# dw08a2s.net
KiCad netlist of a schematic drawn in EAGLE
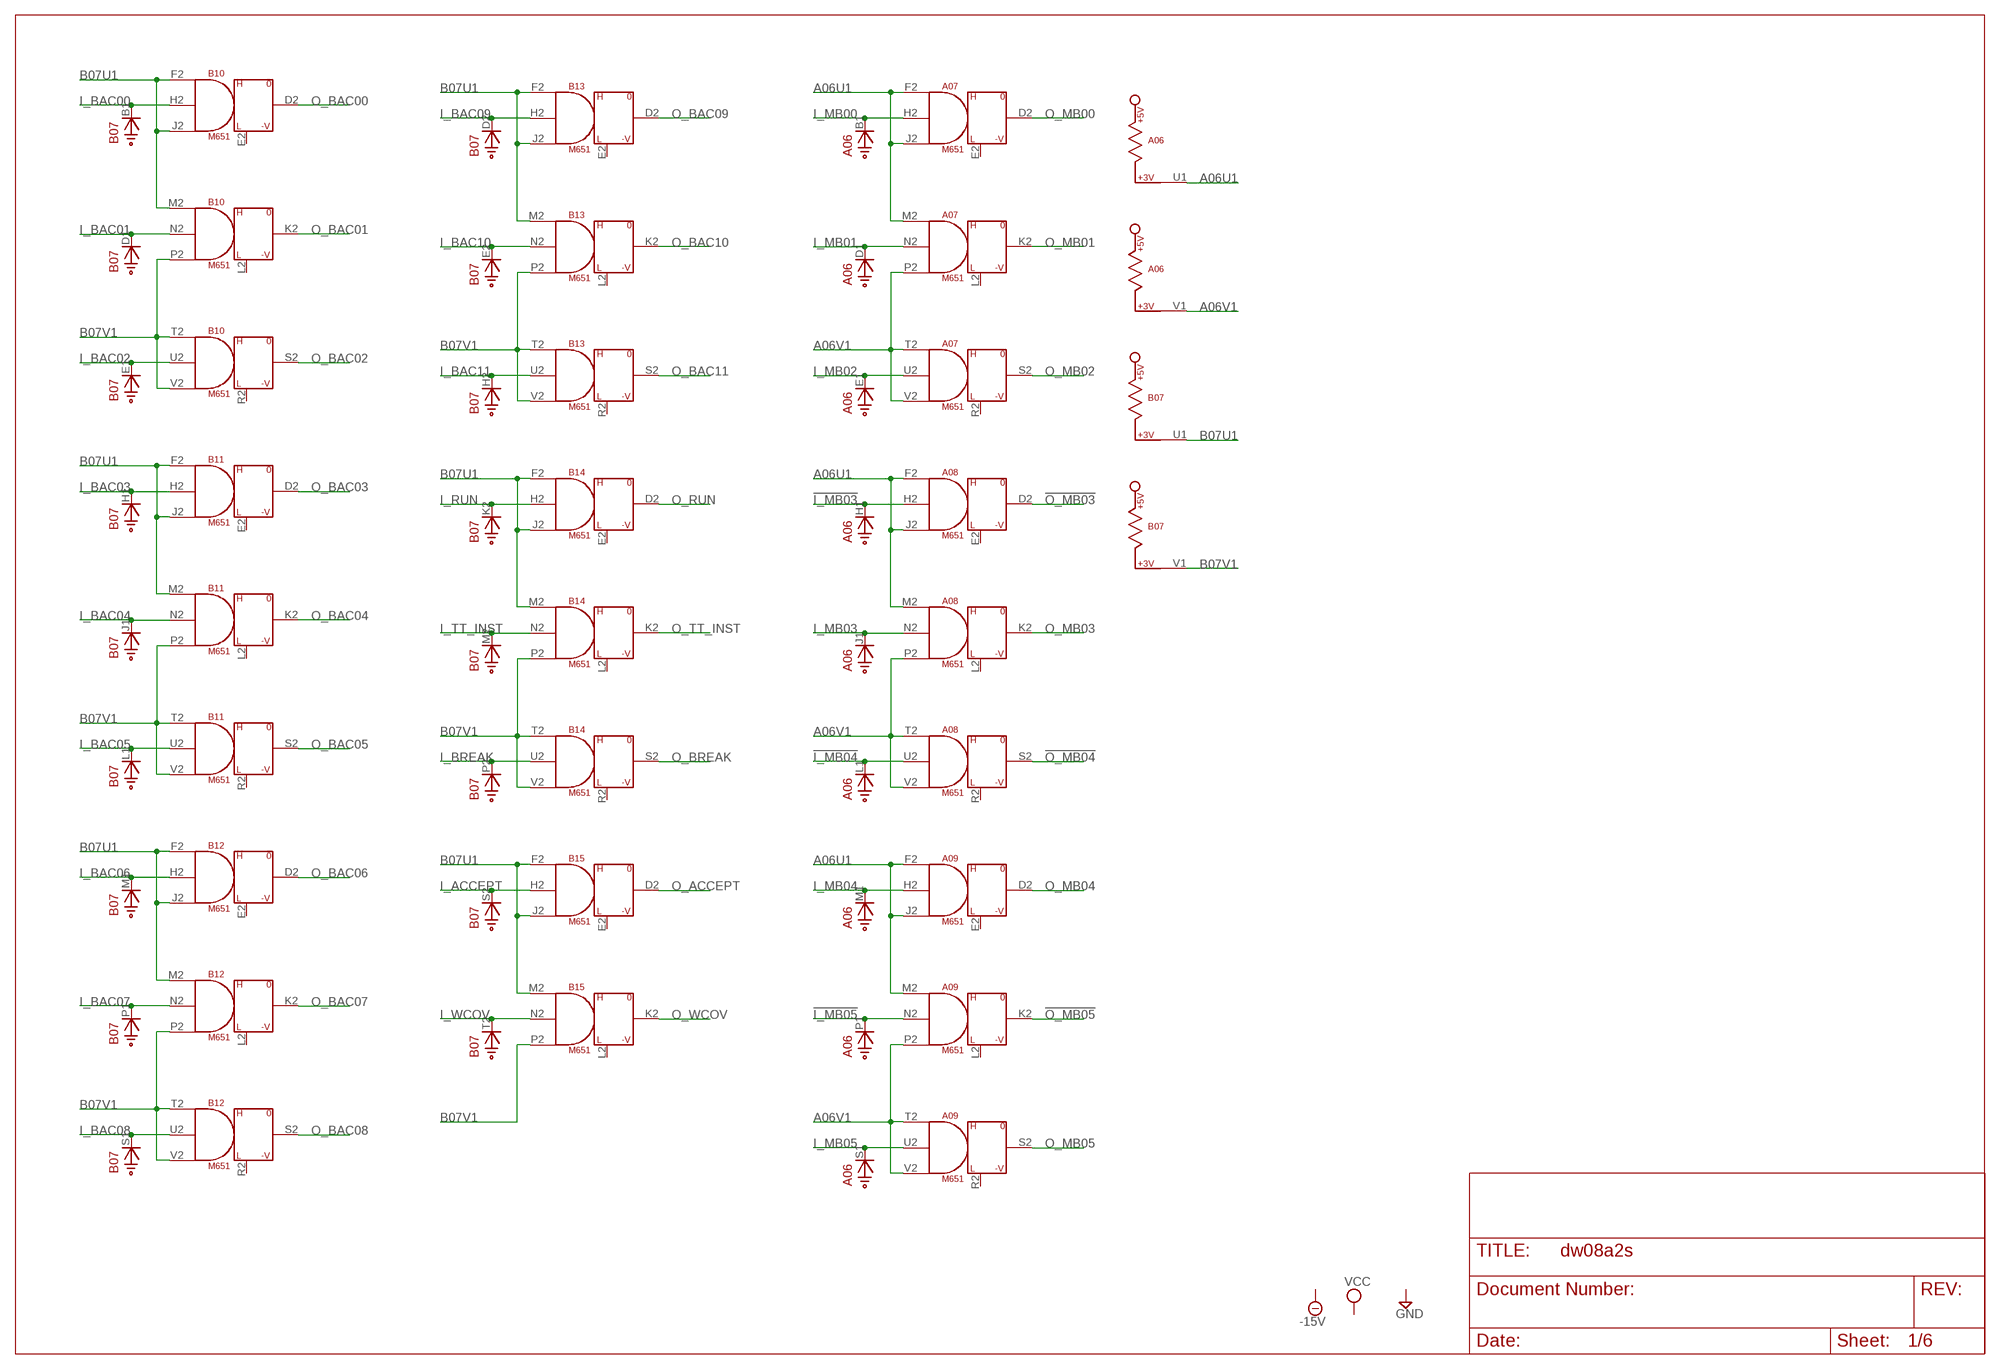
[diagram p0: schematic, sheet 1]
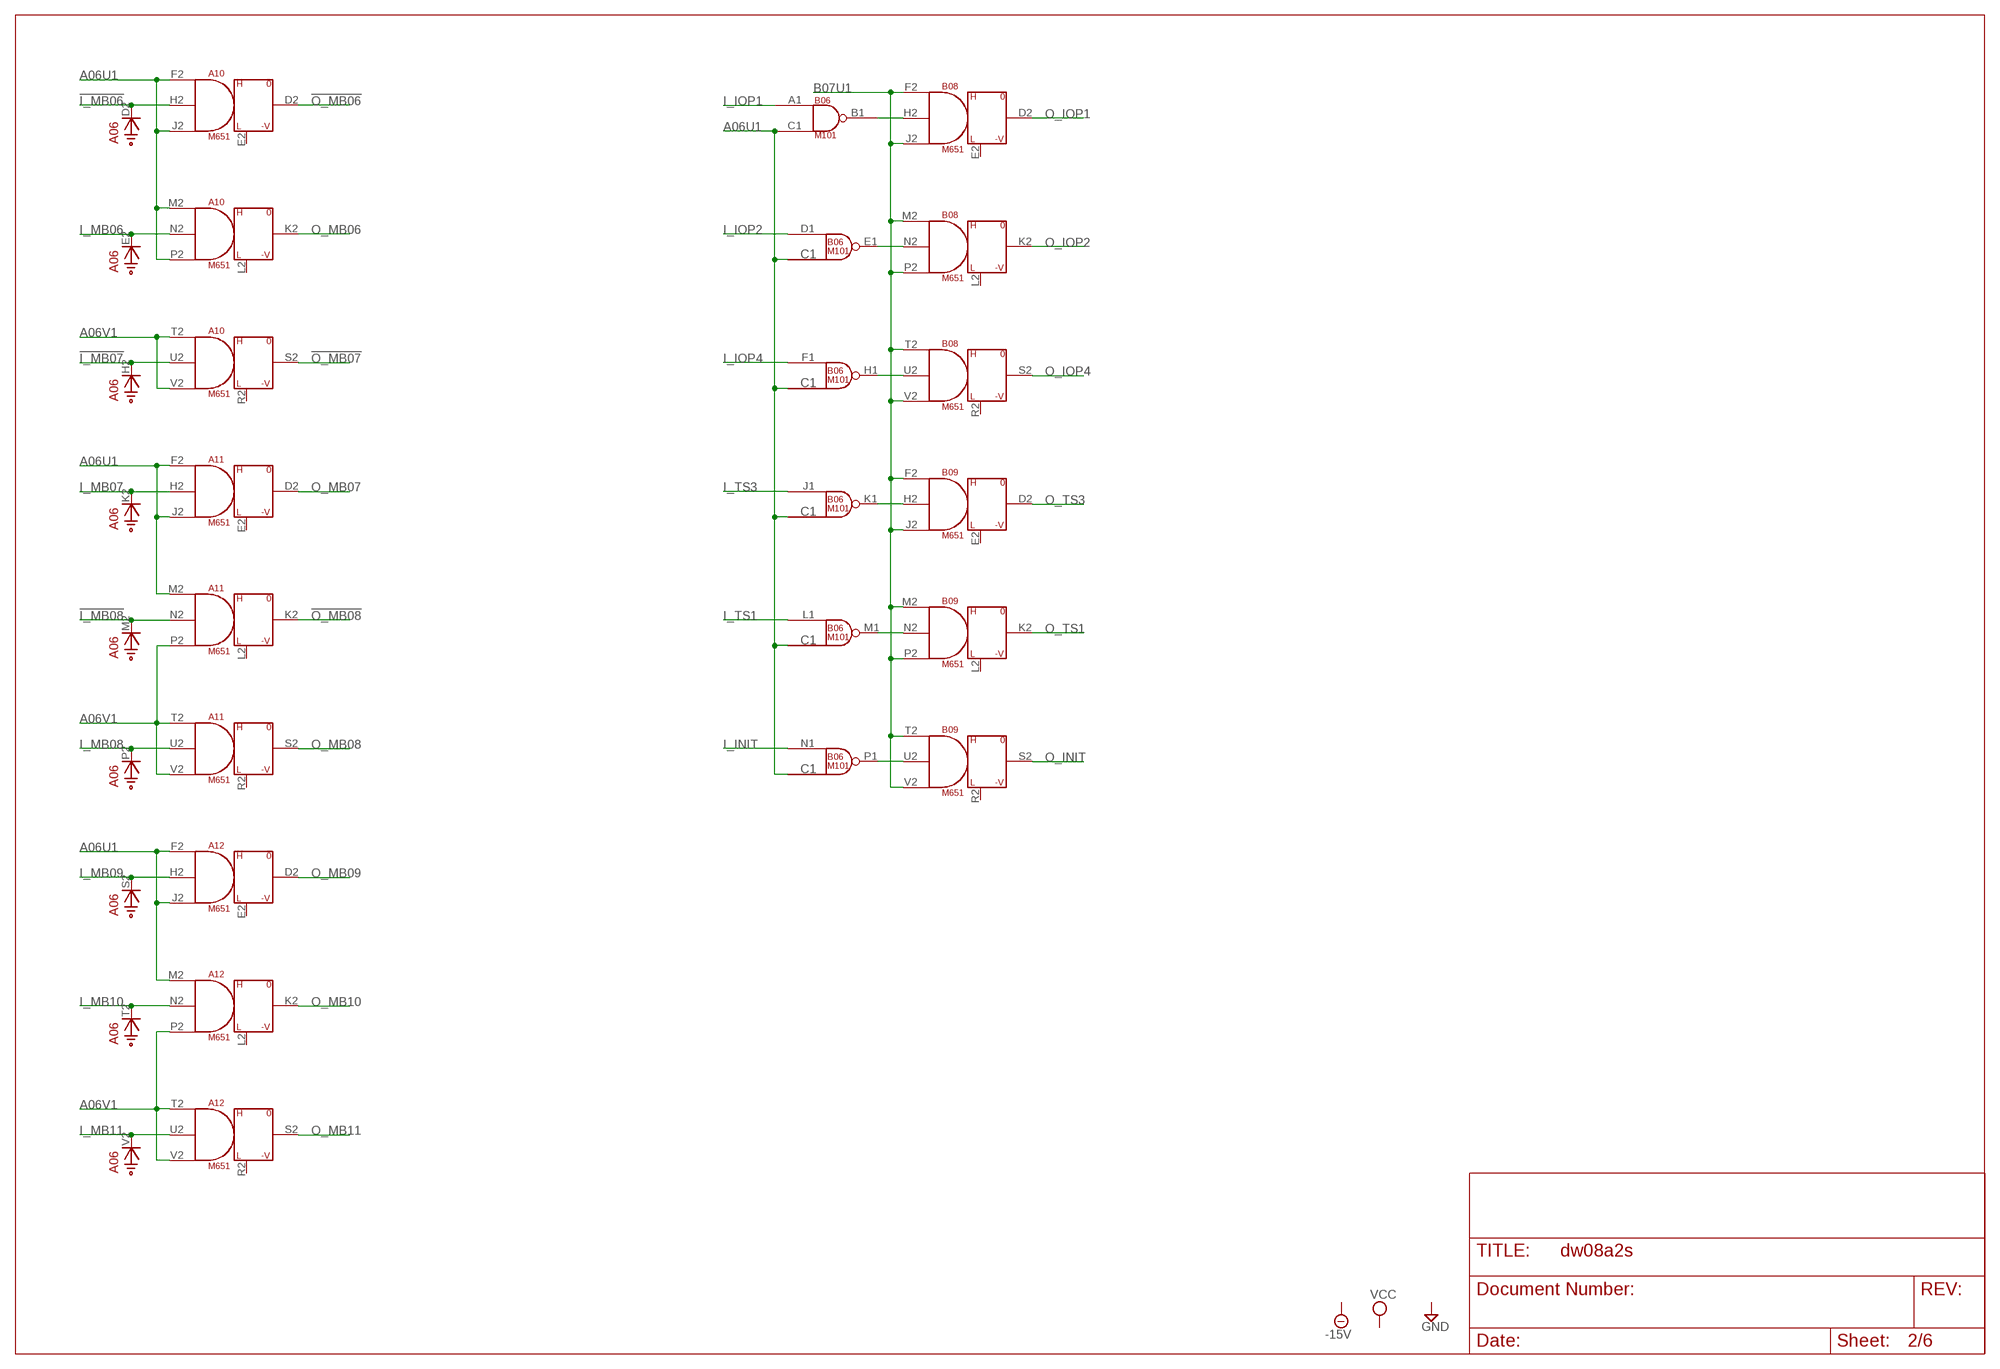
[diagram p1: schematic, sheet 2]
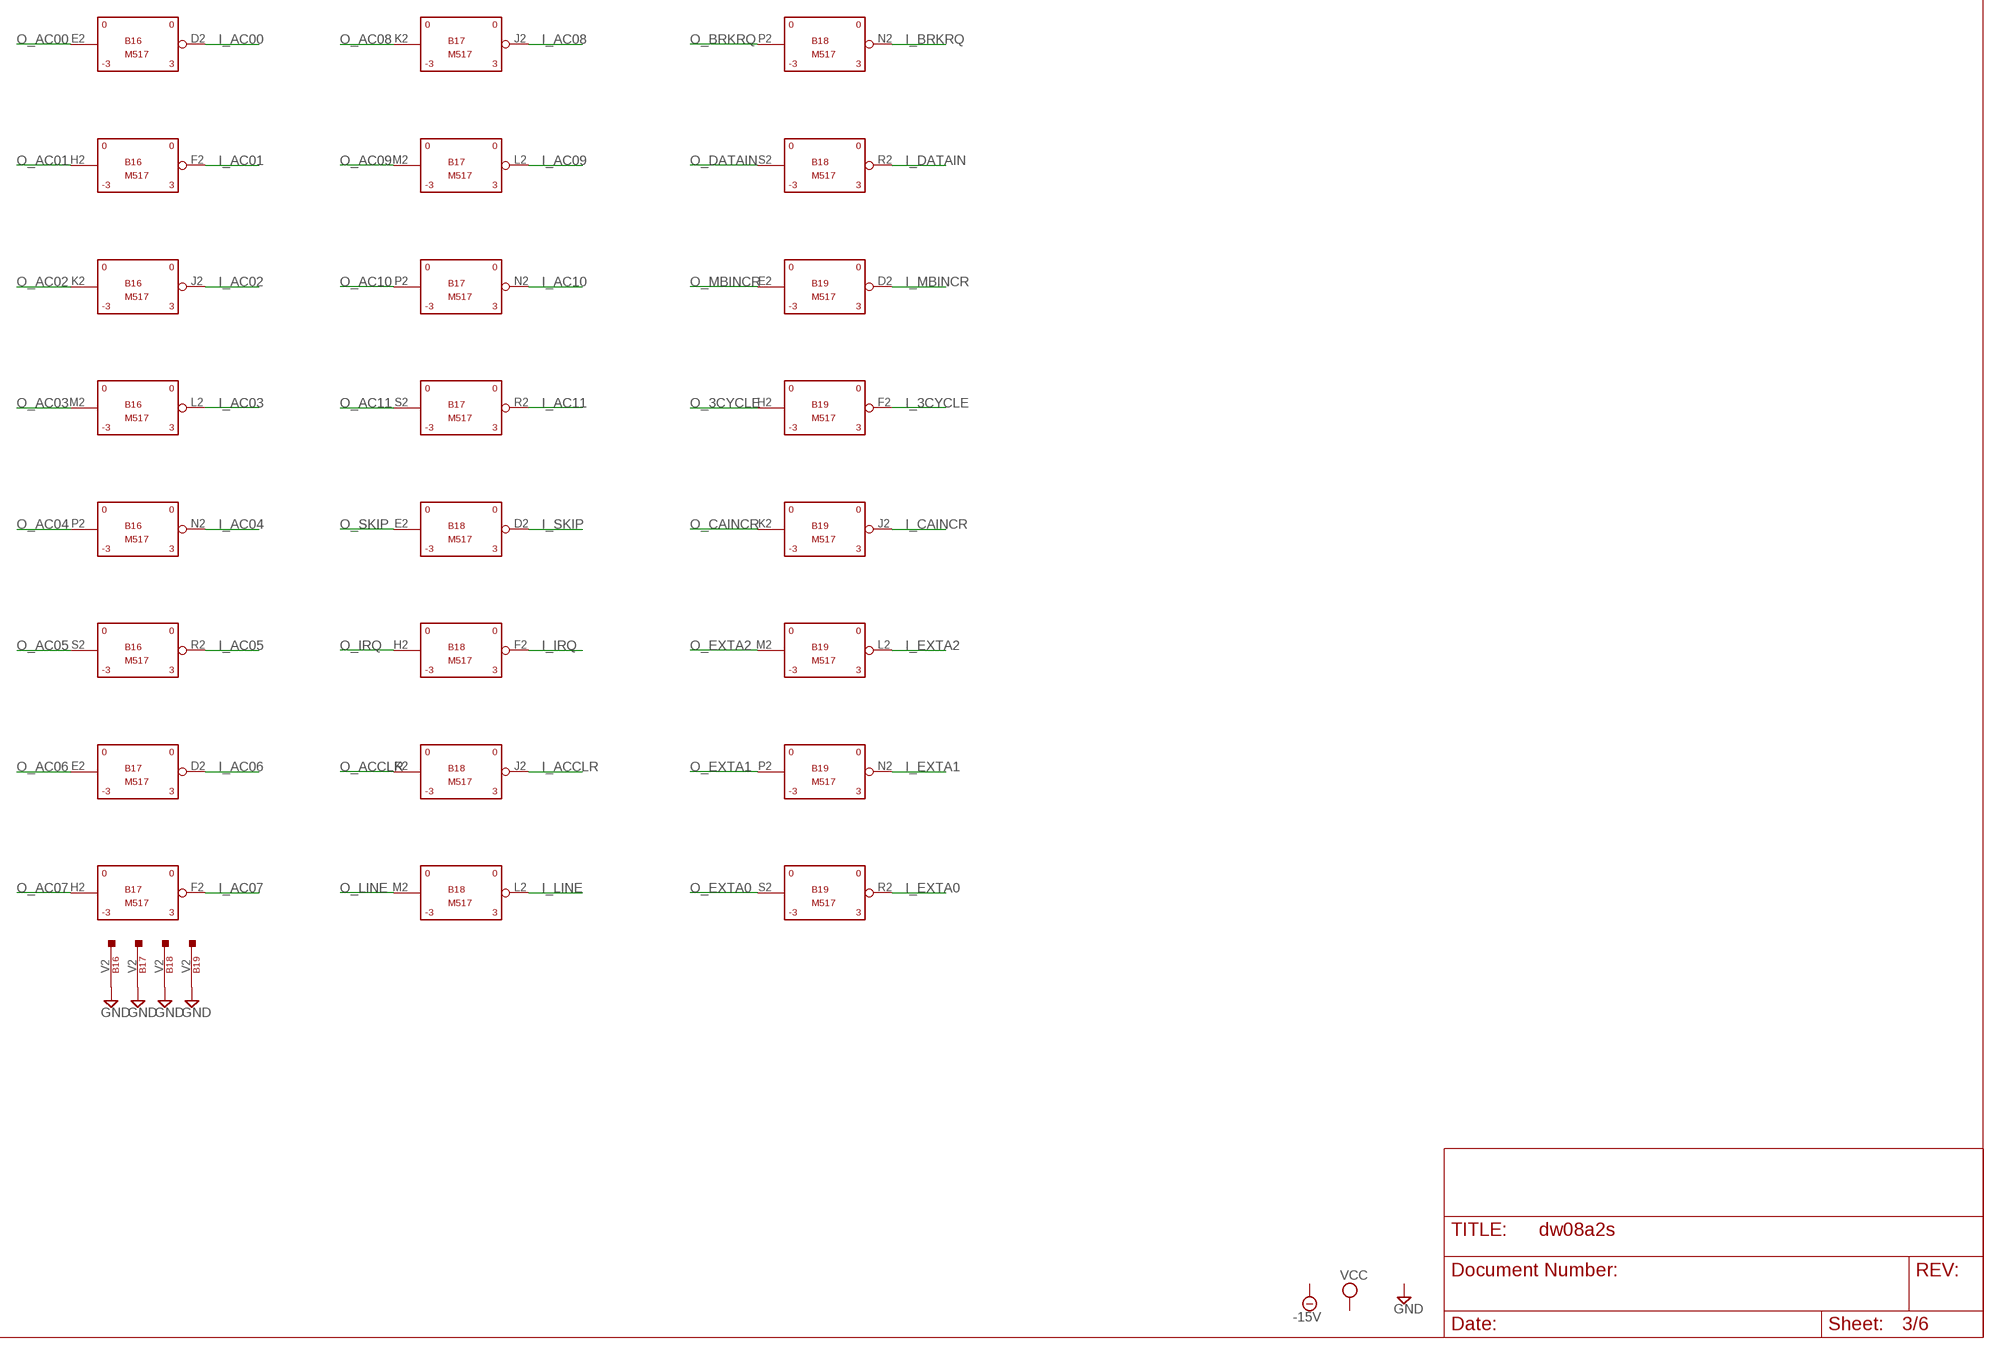
[diagram p2: schematic, sheet 3]
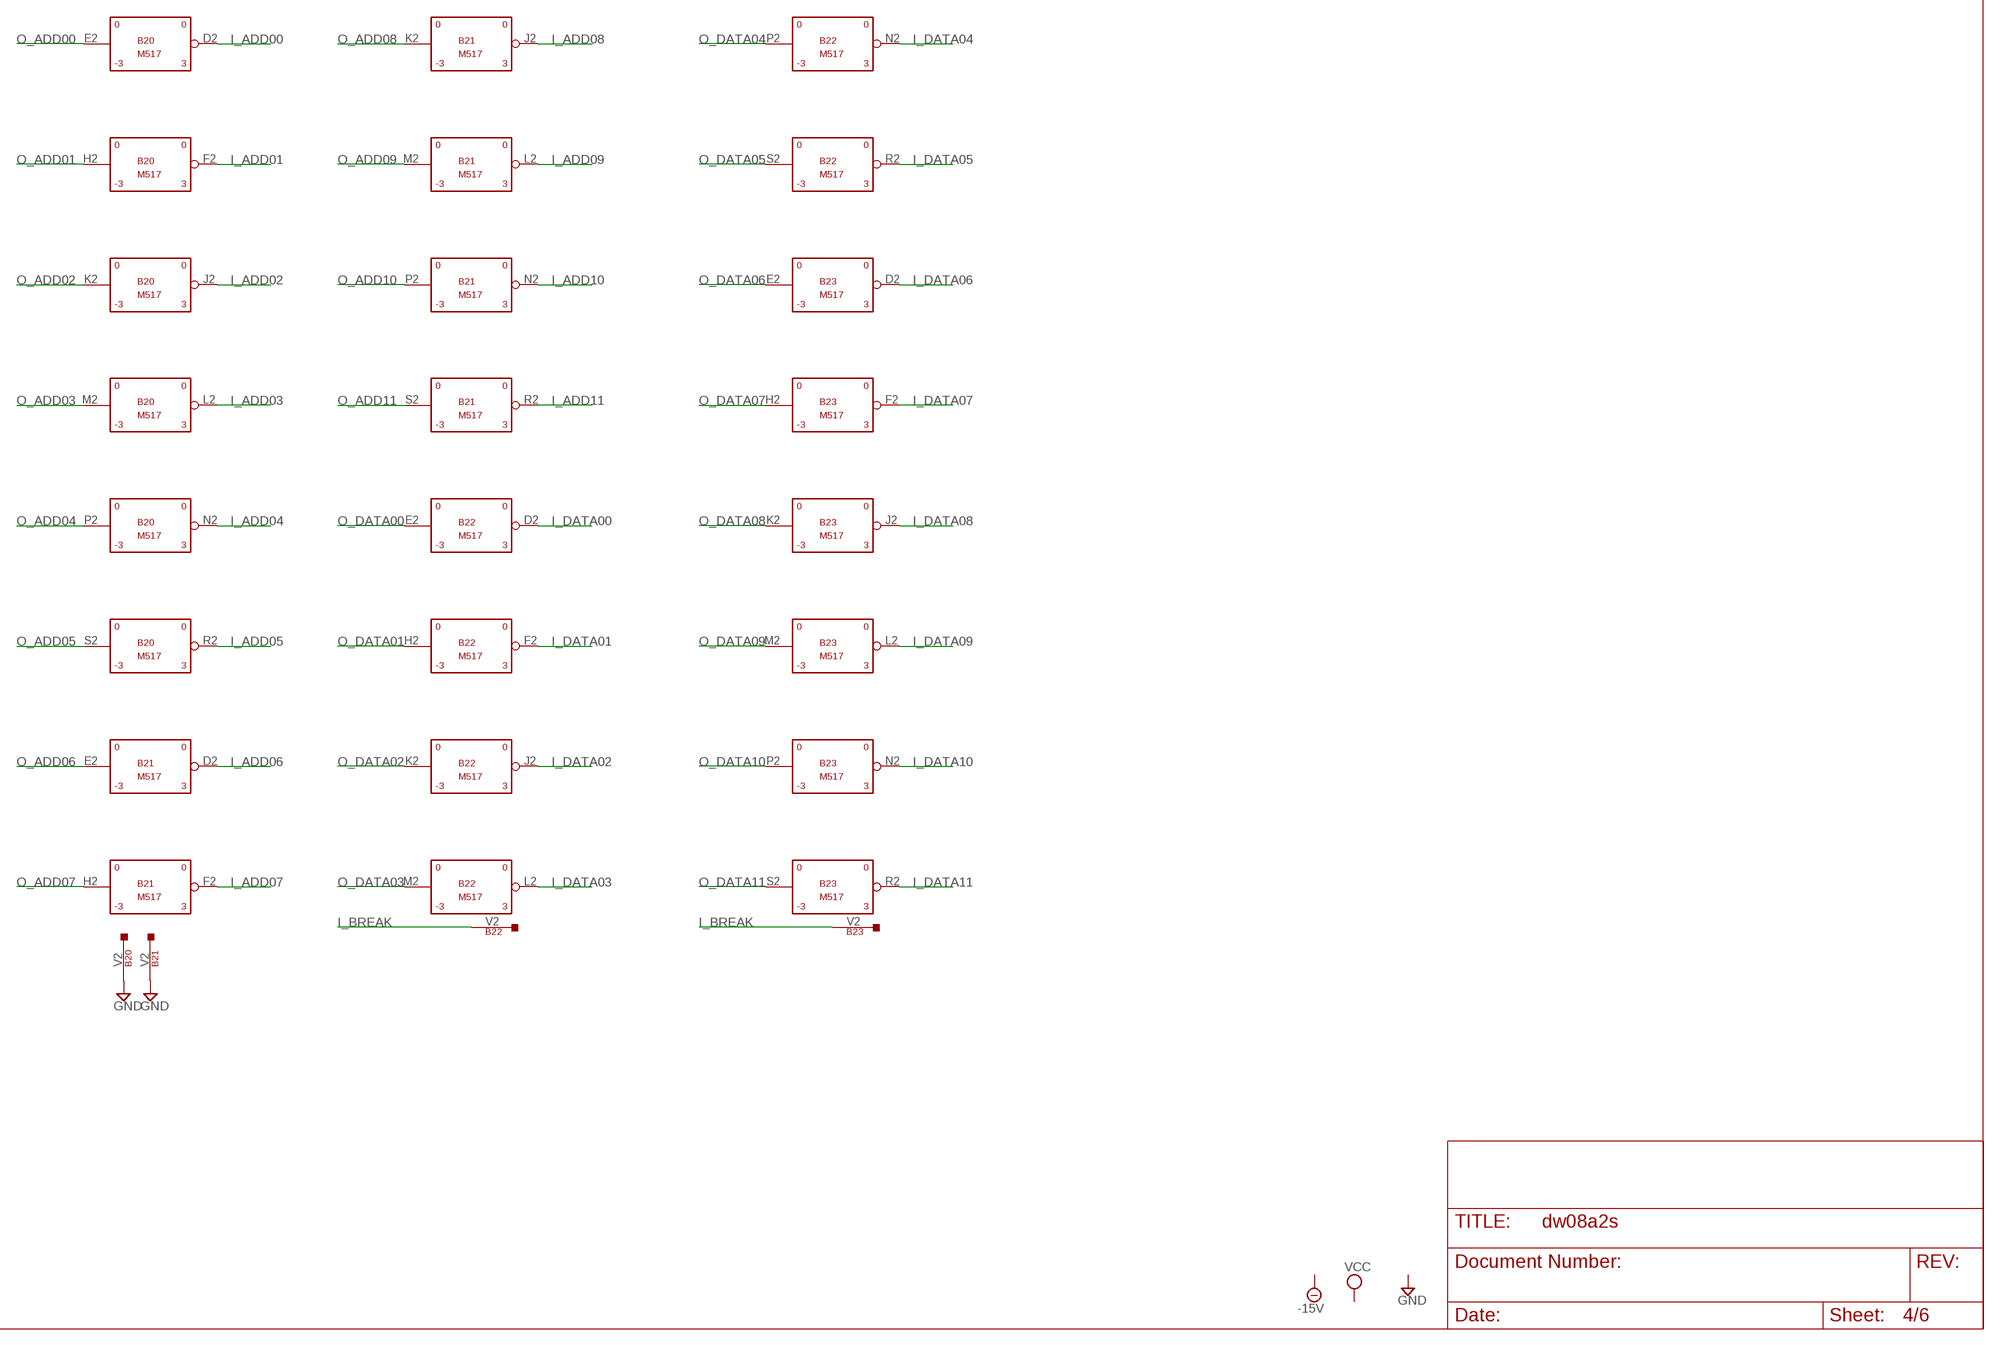
[diagram p3: schematic, sheet 4]
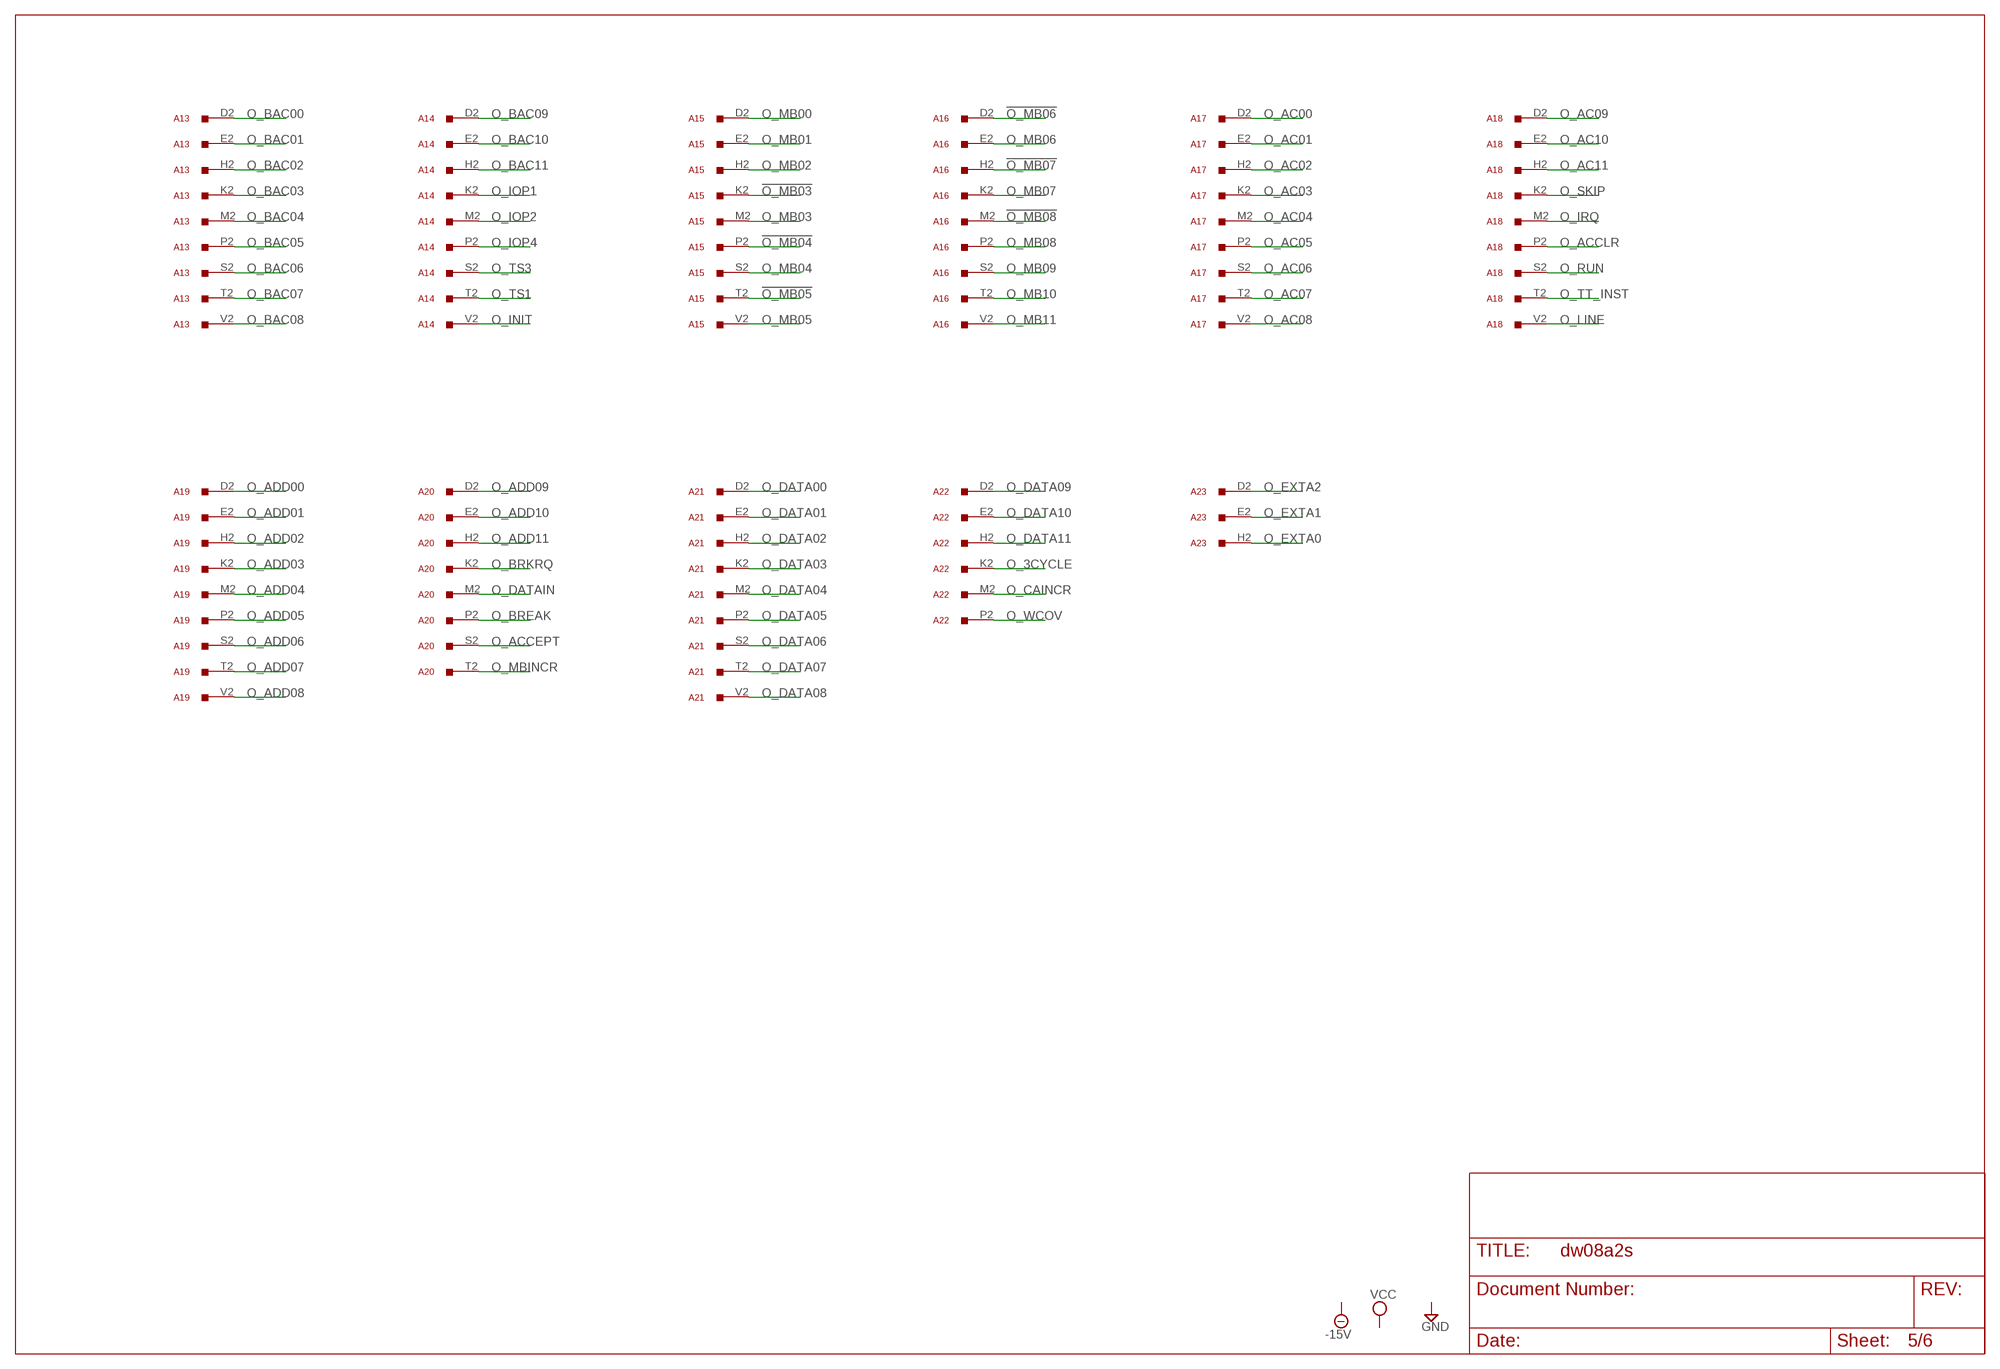
[diagram p4: schematic, sheet 5]
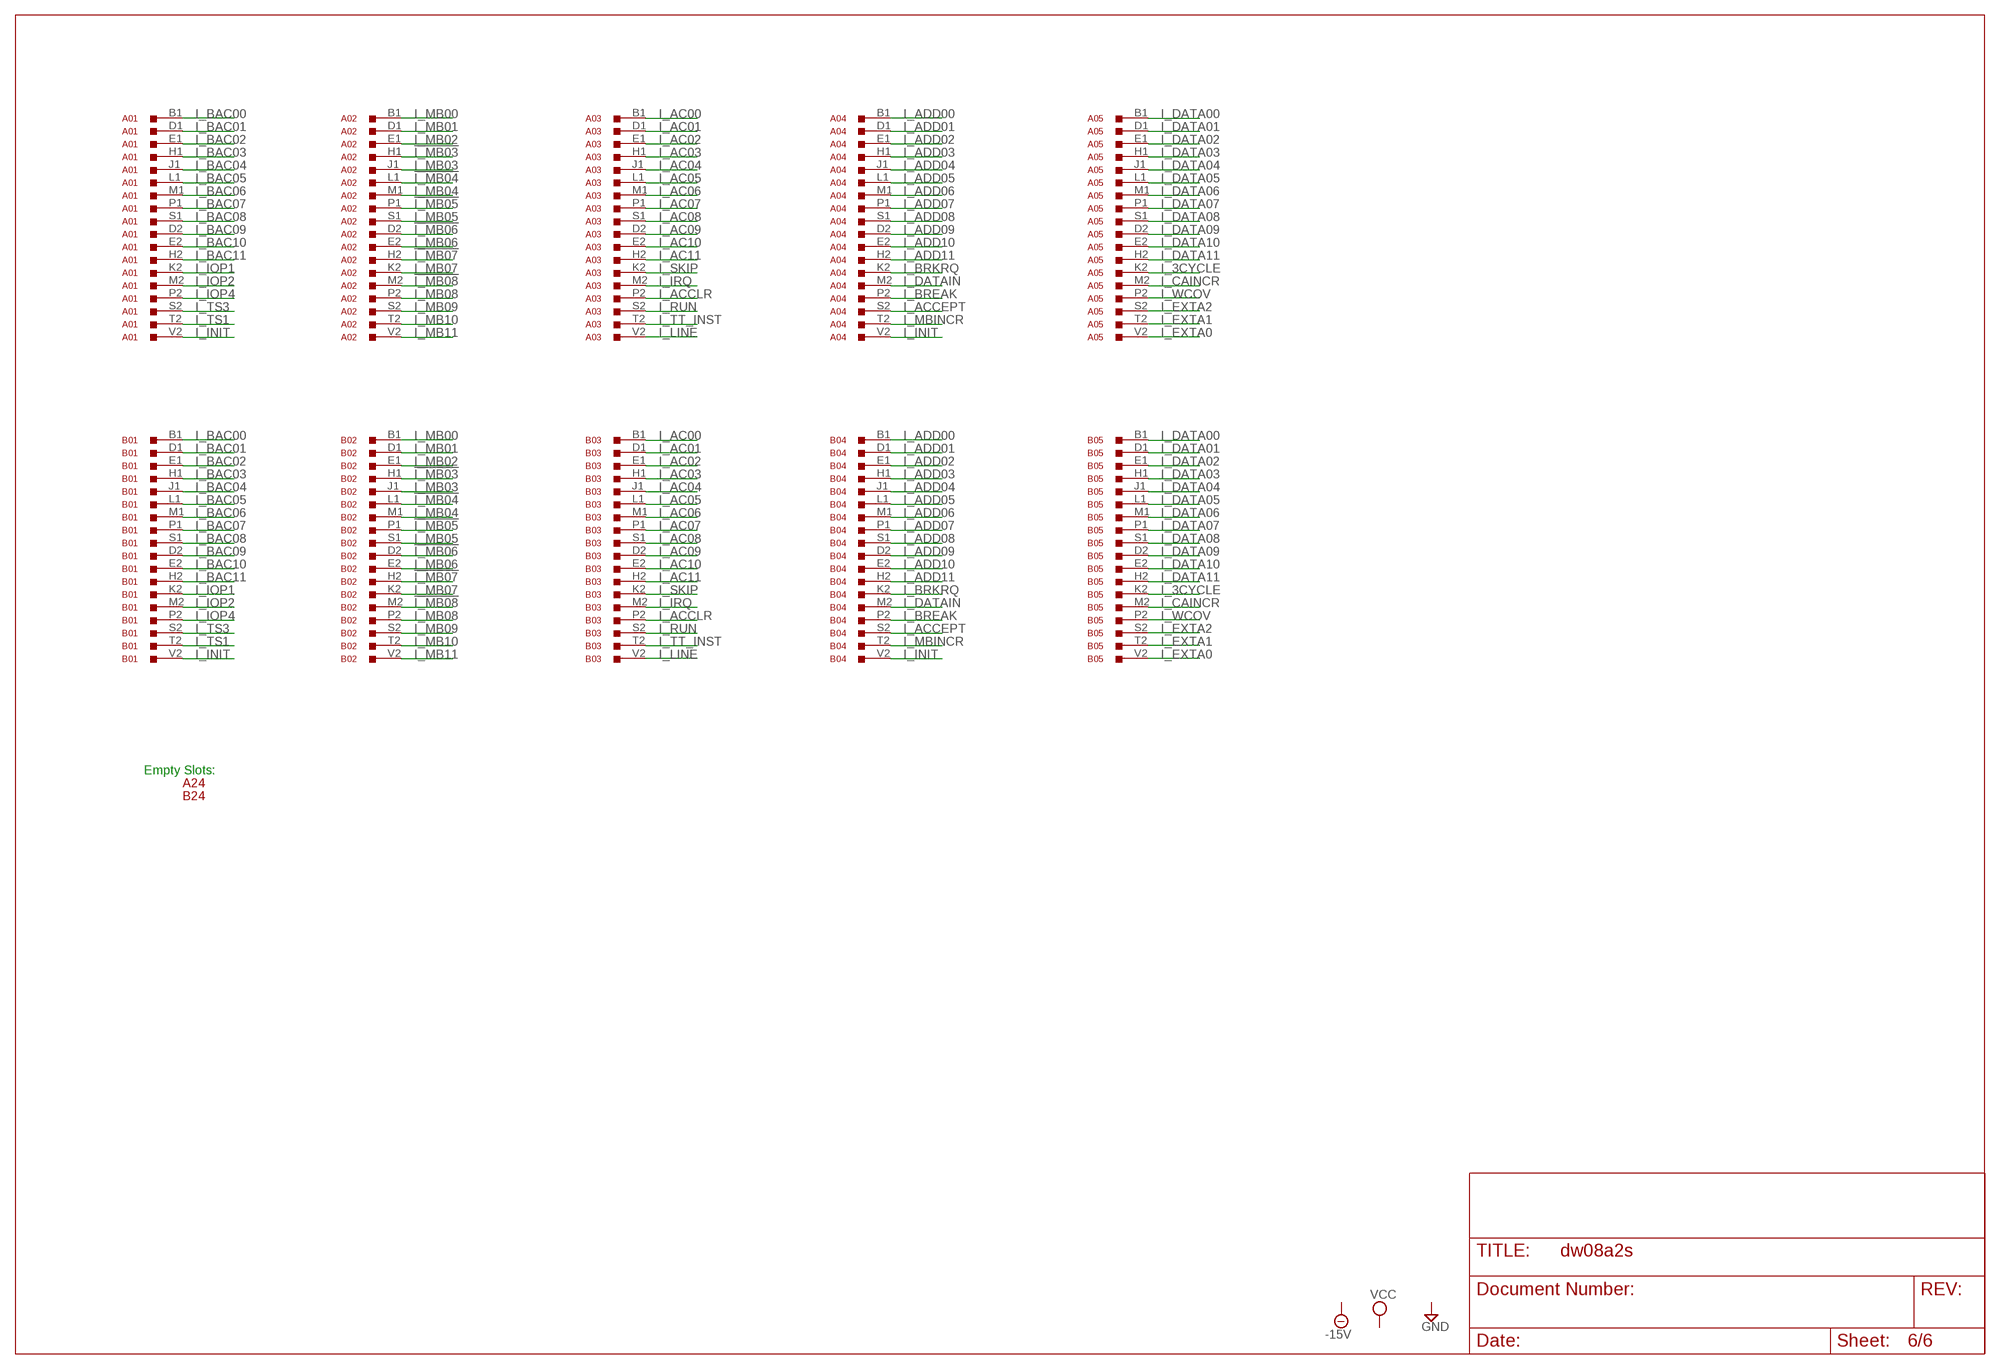
[diagram p5: schematic, sheet 6]

(export (version "E")
  (design (tool "Eeschema 10.0.6"))
  (components
    (comp (ref "B16")
      (value "M517")
      (footprint "eagle-import:H807")
      (libsource (lib "eagle-import") (part "M517"))
    )
    (comp (ref "B17")
      (value "M517")
      (footprint "eagle-import:H807")
      (libsource (lib "eagle-import") (part "M517"))
    )
    (comp (ref "B18")
      (value "M517")
      (footprint "eagle-import:H807")
      (libsource (lib "eagle-import") (part "M517"))
    )
    (comp (ref "B19")
      (value "M517")
      (footprint "eagle-import:H807")
      (libsource (lib "eagle-import") (part "M517"))
    )
    (comp (ref "A13")
      (value "W011")
      (footprint "eagle-import:H807")
      (libsource (lib "eagle-import") (part "W011"))
    )
    (comp (ref "A14")
      (value "W011")
      (footprint "eagle-import:H807")
      (libsource (lib "eagle-import") (part "W011"))
    )
    (comp (ref "A15")
      (value "W011")
      (footprint "eagle-import:H807")
      (libsource (lib "eagle-import") (part "W011"))
    )
    (comp (ref "A16")
      (value "W011")
      (footprint "eagle-import:H807")
      (libsource (lib "eagle-import") (part "W011"))
    )
    (comp (ref "A17")
      (value "W011")
      (footprint "eagle-import:H807")
      (libsource (lib "eagle-import") (part "W011"))
    )
    (comp (ref "A18")
      (value "W011")
      (footprint "eagle-import:H807")
      (libsource (lib "eagle-import") (part "W011"))
    )
    (comp (ref "A19")
      (value "W011")
      (footprint "eagle-import:H807")
      (libsource (lib "eagle-import") (part "W011"))
    )
    (comp (ref "A20")
      (value "W011")
      (footprint "eagle-import:H807")
      (libsource (lib "eagle-import") (part "W011"))
    )
    (comp (ref "A21")
      (value "W011")
      (footprint "eagle-import:H807")
      (libsource (lib "eagle-import") (part "W011"))
    )
    (comp (ref "A22")
      (value "W011")
      (footprint "eagle-import:H807")
      (libsource (lib "eagle-import") (part "W011"))
    )
    (comp (ref "A23")
      (value "W011")
      (footprint "eagle-import:H807")
      (libsource (lib "eagle-import") (part "W011"))
    )
    (comp (ref "B20")
      (value "M517")
      (footprint "eagle-import:H807")
      (libsource (lib "eagle-import") (part "M517"))
    )
    (comp (ref "B21")
      (value "M517")
      (footprint "eagle-import:H807")
      (libsource (lib "eagle-import") (part "M517"))
    )
    (comp (ref "B22")
      (value "M517")
      (footprint "eagle-import:H807")
      (libsource (lib "eagle-import") (part "M517"))
    )
    (comp (ref "B23")
      (value "M517")
      (footprint "eagle-import:H807")
      (libsource (lib "eagle-import") (part "M517"))
    )
    (comp (ref "A06")
      (value "M907")
      (footprint "eagle-import:H807")
      (libsource (lib "eagle-import") (part "M907"))
    )
    (comp (ref "A10")
      (value "M651")
      (footprint "eagle-import:H807")
      (libsource (lib "eagle-import") (part "M651"))
    )
    (comp (ref "A11")
      (value "M651")
      (footprint "eagle-import:H807")
      (libsource (lib "eagle-import") (part "M651"))
    )
    (comp (ref "A12")
      (value "M651")
      (footprint "eagle-import:H807")
      (libsource (lib "eagle-import") (part "M651"))
    )
    (comp (ref "B06")
      (value "M101")
      (footprint "eagle-import:H807")
      (libsource (lib "eagle-import") (part "M101"))
    )
    (comp (ref "B08")
      (value "M651")
      (footprint "eagle-import:H807")
      (libsource (lib "eagle-import") (part "M651"))
    )
    (comp (ref "B09")
      (value "M651")
      (footprint "eagle-import:H807")
      (libsource (lib "eagle-import") (part "M651"))
    )
    (comp (ref "A01")
      (value "M903")
      (footprint "eagle-import:H807")
      (libsource (lib "eagle-import") (part "M903"))
    )
    (comp (ref "A02")
      (value "M903")
      (footprint "eagle-import:H807")
      (libsource (lib "eagle-import") (part "M903"))
    )
    (comp (ref "A03")
      (value "M903")
      (footprint "eagle-import:H807")
      (libsource (lib "eagle-import") (part "M903"))
    )
    (comp (ref "A04")
      (value "M903")
      (footprint "eagle-import:H807")
      (libsource (lib "eagle-import") (part "M903"))
    )
    (comp (ref "A05")
      (value "M903")
      (footprint "eagle-import:H807")
      (libsource (lib "eagle-import") (part "M903"))
    )
    (comp (ref "A24")
      (value "H807")
      (footprint "eagle-import:H807")
      (libsource (lib "eagle-import") (part "H807"))
    )
    (comp (ref "B01")
      (value "M903")
      (footprint "eagle-import:H807")
      (libsource (lib "eagle-import") (part "M903"))
    )
    (comp (ref "B02")
      (value "M903")
      (footprint "eagle-import:H807")
      (libsource (lib "eagle-import") (part "M903"))
    )
    (comp (ref "B03")
      (value "M903")
      (footprint "eagle-import:H807")
      (libsource (lib "eagle-import") (part "M903"))
    )
    (comp (ref "B04")
      (value "M903")
      (footprint "eagle-import:H807")
      (libsource (lib "eagle-import") (part "M903"))
    )
    (comp (ref "B05")
      (value "M903")
      (footprint "eagle-import:H807")
      (libsource (lib "eagle-import") (part "M903"))
    )
    (comp (ref "B24")
      (value "H807")
      (footprint "eagle-import:H807")
      (libsource (lib "eagle-import") (part "H807"))
    )
    (comp (ref "A07")
      (value "M651")
      (footprint "eagle-import:H807")
      (libsource (lib "eagle-import") (part "M651"))
    )
    (comp (ref "A08")
      (value "M651")
      (footprint "eagle-import:H807")
      (libsource (lib "eagle-import") (part "M651"))
    )
    (comp (ref "A09")
      (value "M651")
      (footprint "eagle-import:H807")
      (libsource (lib "eagle-import") (part "M651"))
    )
    (comp (ref "B07")
      (value "M907")
      (footprint "eagle-import:H807")
      (libsource (lib "eagle-import") (part "M907"))
    )
    (comp (ref "B10")
      (value "M651")
      (footprint "eagle-import:H807")
      (libsource (lib "eagle-import") (part "M651"))
    )
    (comp (ref "B11")
      (value "M651")
      (footprint "eagle-import:H807")
      (libsource (lib "eagle-import") (part "M651"))
    )
    (comp (ref "B12")
      (value "M651")
      (footprint "eagle-import:H807")
      (libsource (lib "eagle-import") (part "M651"))
    )
    (comp (ref "B13")
      (value "M651")
      (footprint "eagle-import:H807")
      (libsource (lib "eagle-import") (part "M651"))
    )
    (comp (ref "B14")
      (value "M651")
      (footprint "eagle-import:H807")
      (libsource (lib "eagle-import") (part "M651"))
    )
    (comp (ref "B15")
      (value "M651")
      (footprint "eagle-import:H807")
      (libsource (lib "eagle-import") (part "M651"))
    )
  )
  (nets
    (net (code "2") (name "A06U1") (class "Default")
      (node (ref "A06") (pin "U1") (pinfunction "P$1_U1") (pintype "passive"))
      (node (ref "A07") (pin "F2") (pinfunction "IN1_F2") (pintype "input"))
      (node (ref "A07") (pin "J2") (pinfunction "IN3_J2") (pintype "input"))
      (node (ref "A07") (pin "M2") (pinfunction "IN1_M2") (pintype "input"))
      (node (ref "A08") (pin "F2") (pinfunction "IN1_F2") (pintype "input"))
      (node (ref "A08") (pin "J2") (pinfunction "IN3_J2") (pintype "input"))
      (node (ref "A08") (pin "M2") (pinfunction "IN1_M2") (pintype "input"))
      (node (ref "A09") (pin "F2") (pinfunction "IN1_F2") (pintype "input"))
      (node (ref "A09") (pin "J2") (pinfunction "IN3_J2") (pintype "input"))
      (node (ref "A09") (pin "M2") (pinfunction "IN1_M2") (pintype "input"))
      (node (ref "A10") (pin "F2") (pinfunction "IN1_F2") (pintype "input"))
      (node (ref "A10") (pin "J2") (pinfunction "IN3_J2") (pintype "input"))
      (node (ref "A10") (pin "M2") (pinfunction "IN1_M2") (pintype "input"))
      (node (ref "A10") (pin "P2") (pinfunction "IN3_P2") (pintype "input"))
      (node (ref "A11") (pin "F2") (pinfunction "IN1_F2") (pintype "input"))
      (node (ref "A11") (pin "J2") (pinfunction "IN3_J2") (pintype "input"))
      (node (ref "A11") (pin "M2") (pinfunction "IN1_M2") (pintype "input"))
      (node (ref "A12") (pin "F2") (pinfunction "IN1_F2") (pintype "input"))
      (node (ref "A12") (pin "J2") (pinfunction "IN3_J2") (pintype "input"))
      (node (ref "A12") (pin "M2") (pinfunction "IN1_M2") (pintype "input"))
      (node (ref "B06") (pin "C1") (pinfunction "IN2_C1") (pintype "input"))
    )
    (net (code "3") (name "A06V1") (class "Default")
      (node (ref "A06") (pin "V1") (pinfunction "P$1_V1") (pintype "passive"))
      (node (ref "A07") (pin "P2") (pinfunction "IN3_P2") (pintype "input"))
      (node (ref "A07") (pin "T2") (pinfunction "IN1_T2") (pintype "input"))
      (node (ref "A07") (pin "V2") (pinfunction "IN3_V2") (pintype "input"))
      (node (ref "A08") (pin "P2") (pinfunction "IN3_P2") (pintype "input"))
      (node (ref "A08") (pin "T2") (pinfunction "IN1_T2") (pintype "input"))
      (node (ref "A08") (pin "V2") (pinfunction "IN3_V2") (pintype "input"))
      (node (ref "A09") (pin "P2") (pinfunction "IN3_P2") (pintype "input"))
      (node (ref "A09") (pin "T2") (pinfunction "IN1_T2") (pintype "input"))
      (node (ref "A09") (pin "V2") (pinfunction "IN3_V2") (pintype "input"))
      (node (ref "A10") (pin "T2") (pinfunction "IN1_T2") (pintype "input"))
      (node (ref "A10") (pin "V2") (pinfunction "IN3_V2") (pintype "input"))
      (node (ref "A11") (pin "P2") (pinfunction "IN3_P2") (pintype "input"))
      (node (ref "A11") (pin "T2") (pinfunction "IN1_T2") (pintype "input"))
      (node (ref "A11") (pin "V2") (pinfunction "IN3_V2") (pintype "input"))
      (node (ref "A12") (pin "P2") (pinfunction "IN3_P2") (pintype "input"))
      (node (ref "A12") (pin "T2") (pinfunction "IN1_T2") (pintype "input"))
      (node (ref "A12") (pin "V2") (pinfunction "IN3_V2") (pintype "input"))
    )
    (net (code "4") (name "B07U1") (class "Default")
      (node (ref "B07") (pin "U1") (pinfunction "P$1_U1") (pintype "passive"))
      (node (ref "B08") (pin "F2") (pinfunction "IN1_F2") (pintype "input"))
      (node (ref "B08") (pin "J2") (pinfunction "IN3_J2") (pintype "input"))
      (node (ref "B08") (pin "M2") (pinfunction "IN1_M2") (pintype "input"))
      (node (ref "B08") (pin "P2") (pinfunction "IN3_P2") (pintype "input"))
      (node (ref "B08") (pin "T2") (pinfunction "IN1_T2") (pintype "input"))
      (node (ref "B08") (pin "V2") (pinfunction "IN3_V2") (pintype "input"))
      (node (ref "B09") (pin "F2") (pinfunction "IN1_F2") (pintype "input"))
      (node (ref "B09") (pin "J2") (pinfunction "IN3_J2") (pintype "input"))
      (node (ref "B09") (pin "M2") (pinfunction "IN1_M2") (pintype "input"))
      (node (ref "B09") (pin "P2") (pinfunction "IN3_P2") (pintype "input"))
      (node (ref "B09") (pin "T2") (pinfunction "IN1_T2") (pintype "input"))
      (node (ref "B09") (pin "V2") (pinfunction "IN3_V2") (pintype "input"))
      (node (ref "B10") (pin "F2") (pinfunction "IN1_F2") (pintype "input"))
      (node (ref "B10") (pin "J2") (pinfunction "IN3_J2") (pintype "input"))
      (node (ref "B10") (pin "M2") (pinfunction "IN1_M2") (pintype "input"))
      (node (ref "B11") (pin "F2") (pinfunction "IN1_F2") (pintype "input"))
      (node (ref "B11") (pin "J2") (pinfunction "IN3_J2") (pintype "input"))
      (node (ref "B11") (pin "M2") (pinfunction "IN1_M2") (pintype "input"))
      (node (ref "B12") (pin "F2") (pinfunction "IN1_F2") (pintype "input"))
      (node (ref "B12") (pin "J2") (pinfunction "IN3_J2") (pintype "input"))
      (node (ref "B12") (pin "M2") (pinfunction "IN1_M2") (pintype "input"))
      (node (ref "B13") (pin "F2") (pinfunction "IN1_F2") (pintype "input"))
      (node (ref "B13") (pin "J2") (pinfunction "IN3_J2") (pintype "input"))
      (node (ref "B13") (pin "M2") (pinfunction "IN1_M2") (pintype "input"))
      (node (ref "B14") (pin "F2") (pinfunction "IN1_F2") (pintype "input"))
      (node (ref "B14") (pin "J2") (pinfunction "IN3_J2") (pintype "input"))
      (node (ref "B14") (pin "M2") (pinfunction "IN1_M2") (pintype "input"))
      (node (ref "B15") (pin "F2") (pinfunction "IN1_F2") (pintype "input"))
      (node (ref "B15") (pin "J2") (pinfunction "IN3_J2") (pintype "input"))
      (node (ref "B15") (pin "M2") (pinfunction "IN1_M2") (pintype "input"))
    )
    (net (code "5") (name "B07V1") (class "Default")
      (node (ref "B07") (pin "V1") (pinfunction "P$1_V1") (pintype "passive"))
      (node (ref "B10") (pin "P2") (pinfunction "IN3_P2") (pintype "input"))
      (node (ref "B10") (pin "T2") (pinfunction "IN1_T2") (pintype "input"))
      (node (ref "B10") (pin "V2") (pinfunction "IN3_V2") (pintype "input"))
      (node (ref "B11") (pin "P2") (pinfunction "IN3_P2") (pintype "input"))
      (node (ref "B11") (pin "T2") (pinfunction "IN1_T2") (pintype "input"))
      (node (ref "B11") (pin "V2") (pinfunction "IN3_V2") (pintype "input"))
      (node (ref "B12") (pin "P2") (pinfunction "IN3_P2") (pintype "input"))
      (node (ref "B12") (pin "T2") (pinfunction "IN1_T2") (pintype "input"))
      (node (ref "B12") (pin "V2") (pinfunction "IN3_V2") (pintype "input"))
      (node (ref "B13") (pin "P2") (pinfunction "IN3_P2") (pintype "input"))
      (node (ref "B13") (pin "T2") (pinfunction "IN1_T2") (pintype "input"))
      (node (ref "B13") (pin "V2") (pinfunction "IN3_V2") (pintype "input"))
      (node (ref "B14") (pin "P2") (pinfunction "IN3_P2") (pintype "input"))
      (node (ref "B14") (pin "T2") (pinfunction "IN1_T2") (pintype "input"))
      (node (ref "B14") (pin "V2") (pinfunction "IN3_V2") (pintype "input"))
      (node (ref "B15") (pin "P2") (pinfunction "IN3_P2") (pintype "input"))
    )
    (net (code "6") (name "GND") (class "Default")
      (node (ref "B16") (pin "V2") (pinfunction "P$1_V2") (pintype "input"))
      (node (ref "B17") (pin "V2") (pinfunction "P$1_V2") (pintype "input"))
      (node (ref "B18") (pin "V2") (pinfunction "P$1_V2") (pintype "input"))
      (node (ref "B19") (pin "V2") (pinfunction "P$1_V2") (pintype "input"))
      (node (ref "B20") (pin "V2") (pinfunction "P$1_V2") (pintype "input"))
      (node (ref "B21") (pin "V2") (pinfunction "P$1_V2") (pintype "input"))
    )
    (net (code "7") (name "I_3CYCLE") (class "Default")
      (node (ref "A05") (pin "K2") (pinfunction "P$2_K2") (pintype "bidirectional"))
      (node (ref "B05") (pin "K2") (pinfunction "P$2_K2") (pintype "bidirectional"))
      (node (ref "B19") (pin "F2") (pinfunction "OUT_F2") (pintype "output"))
    )
    (net (code "8") (name "I_AC00") (class "Default")
      (node (ref "A03") (pin "B1") (pinfunction "P$2_B1") (pintype "bidirectional"))
      (node (ref "B03") (pin "B1") (pinfunction "P$2_B1") (pintype "bidirectional"))
      (node (ref "B16") (pin "D2") (pinfunction "OUT_D2") (pintype "output"))
    )
    (net (code "9") (name "I_AC01") (class "Default")
      (node (ref "A03") (pin "D1") (pinfunction "P$2_D1") (pintype "bidirectional"))
      (node (ref "B03") (pin "D1") (pinfunction "P$2_D1") (pintype "bidirectional"))
      (node (ref "B16") (pin "F2") (pinfunction "OUT_F2") (pintype "output"))
    )
    (net (code "10") (name "I_AC02") (class "Default")
      (node (ref "A03") (pin "E1") (pinfunction "P$2_E1") (pintype "bidirectional"))
      (node (ref "B03") (pin "E1") (pinfunction "P$2_E1") (pintype "bidirectional"))
      (node (ref "B16") (pin "J2") (pinfunction "OUT_J2") (pintype "output"))
    )
    (net (code "11") (name "I_AC03") (class "Default")
      (node (ref "A03") (pin "H1") (pinfunction "P$2_H1") (pintype "bidirectional"))
      (node (ref "B03") (pin "H1") (pinfunction "P$2_H1") (pintype "bidirectional"))
      (node (ref "B16") (pin "L2") (pinfunction "OUT_L2") (pintype "output"))
    )
    (net (code "12") (name "I_AC04") (class "Default")
      (node (ref "A03") (pin "J1") (pinfunction "P$2_J1") (pintype "bidirectional"))
      (node (ref "B03") (pin "J1") (pinfunction "P$2_J1") (pintype "bidirectional"))
      (node (ref "B16") (pin "N2") (pinfunction "OUT_N2") (pintype "output"))
    )
    (net (code "13") (name "I_AC05") (class "Default")
      (node (ref "A03") (pin "L1") (pinfunction "P$2_L1") (pintype "bidirectional"))
      (node (ref "B03") (pin "L1") (pinfunction "P$2_L1") (pintype "bidirectional"))
      (node (ref "B16") (pin "R2") (pinfunction "OUT_R2") (pintype "output"))
    )
    (net (code "14") (name "I_AC06") (class "Default")
      (node (ref "A03") (pin "M1") (pinfunction "P$2_M1") (pintype "bidirectional"))
      (node (ref "B03") (pin "M1") (pinfunction "P$2_M1") (pintype "bidirectional"))
      (node (ref "B17") (pin "D2") (pinfunction "OUT_D2") (pintype "output"))
    )
    (net (code "15") (name "I_AC07") (class "Default")
      (node (ref "A03") (pin "P1") (pinfunction "P$2_P1") (pintype "bidirectional"))
      (node (ref "B03") (pin "P1") (pinfunction "P$2_P1") (pintype "bidirectional"))
      (node (ref "B17") (pin "F2") (pinfunction "OUT_F2") (pintype "output"))
    )
    (net (code "16") (name "I_AC08") (class "Default")
      (node (ref "A03") (pin "S1") (pinfunction "P$2_S1") (pintype "bidirectional"))
      (node (ref "B03") (pin "S1") (pinfunction "P$2_S1") (pintype "bidirectional"))
      (node (ref "B17") (pin "J2") (pinfunction "OUT_J2") (pintype "output"))
    )
    (net (code "17") (name "I_AC09") (class "Default")
      (node (ref "A03") (pin "D2") (pinfunction "P$2_D2") (pintype "bidirectional"))
      (node (ref "B03") (pin "D2") (pinfunction "P$2_D2") (pintype "bidirectional"))
      (node (ref "B17") (pin "L2") (pinfunction "OUT_L2") (pintype "output"))
    )
    (net (code "18") (name "I_AC10") (class "Default")
      (node (ref "A03") (pin "E2") (pinfunction "P$2_E2") (pintype "bidirectional"))
      (node (ref "B03") (pin "E2") (pinfunction "P$2_E2") (pintype "bidirectional"))
      (node (ref "B17") (pin "N2") (pinfunction "OUT_N2") (pintype "output"))
    )
    (net (code "19") (name "I_AC11") (class "Default")
      (node (ref "A03") (pin "H2") (pinfunction "P$2_H2") (pintype "bidirectional"))
      (node (ref "B03") (pin "H2") (pinfunction "P$2_H2") (pintype "bidirectional"))
      (node (ref "B17") (pin "R2") (pinfunction "OUT_R2") (pintype "output"))
    )
    (net (code "20") (name "I_ACCEPT") (class "Default")
      (node (ref "A04") (pin "S2") (pinfunction "P$2_S2") (pintype "bidirectional"))
      (node (ref "B04") (pin "S2") (pinfunction "P$2_S2") (pintype "bidirectional"))
      (node (ref "B07") (pin "S2") (pinfunction "CATHODE_S2") (pintype "passive"))
      (node (ref "B15") (pin "H2") (pinfunction "IN2_H2") (pintype "input"))
    )
    (net (code "21") (name "I_ACCLR") (class "Default")
      (node (ref "A03") (pin "P2") (pinfunction "P$2_P2") (pintype "bidirectional"))
      (node (ref "B03") (pin "P2") (pinfunction "P$2_P2") (pintype "bidirectional"))
      (node (ref "B18") (pin "J2") (pinfunction "OUT_J2") (pintype "output"))
    )
    (net (code "22") (name "I_ADD00") (class "Default")
      (node (ref "A04") (pin "B1") (pinfunction "P$2_B1") (pintype "bidirectional"))
      (node (ref "B04") (pin "B1") (pinfunction "P$2_B1") (pintype "bidirectional"))
      (node (ref "B20") (pin "D2") (pinfunction "OUT_D2") (pintype "output"))
    )
    (net (code "23") (name "I_ADD01") (class "Default")
      (node (ref "A04") (pin "D1") (pinfunction "P$2_D1") (pintype "bidirectional"))
      (node (ref "B04") (pin "D1") (pinfunction "P$2_D1") (pintype "bidirectional"))
      (node (ref "B20") (pin "F2") (pinfunction "OUT_F2") (pintype "output"))
    )
    (net (code "24") (name "I_ADD02") (class "Default")
      (node (ref "A04") (pin "E1") (pinfunction "P$2_E1") (pintype "bidirectional"))
      (node (ref "B04") (pin "E1") (pinfunction "P$2_E1") (pintype "bidirectional"))
      (node (ref "B20") (pin "J2") (pinfunction "OUT_J2") (pintype "output"))
    )
    (net (code "25") (name "I_ADD03") (class "Default")
      (node (ref "A04") (pin "H1") (pinfunction "P$2_H1") (pintype "bidirectional"))
      (node (ref "B04") (pin "H1") (pinfunction "P$2_H1") (pintype "bidirectional"))
      (node (ref "B20") (pin "L2") (pinfunction "OUT_L2") (pintype "output"))
    )
    (net (code "26") (name "I_ADD04") (class "Default")
      (node (ref "A04") (pin "J1") (pinfunction "P$2_J1") (pintype "bidirectional"))
      (node (ref "B04") (pin "J1") (pinfunction "P$2_J1") (pintype "bidirectional"))
      (node (ref "B20") (pin "N2") (pinfunction "OUT_N2") (pintype "output"))
    )
    (net (code "27") (name "I_ADD05") (class "Default")
      (node (ref "A04") (pin "L1") (pinfunction "P$2_L1") (pintype "bidirectional"))
      (node (ref "B04") (pin "L1") (pinfunction "P$2_L1") (pintype "bidirectional"))
      (node (ref "B20") (pin "R2") (pinfunction "OUT_R2") (pintype "output"))
    )
    (net (code "28") (name "I_ADD06") (class "Default")
      (node (ref "A04") (pin "M1") (pinfunction "P$2_M1") (pintype "bidirectional"))
      (node (ref "B04") (pin "M1") (pinfunction "P$2_M1") (pintype "bidirectional"))
      (node (ref "B21") (pin "D2") (pinfunction "OUT_D2") (pintype "output"))
    )
    (net (code "29") (name "I_ADD07") (class "Default")
      (node (ref "A04") (pin "P1") (pinfunction "P$2_P1") (pintype "bidirectional"))
      (node (ref "B04") (pin "P1") (pinfunction "P$2_P1") (pintype "bidirectional"))
      (node (ref "B21") (pin "F2") (pinfunction "OUT_F2") (pintype "output"))
    )
    (net (code "30") (name "I_ADD08") (class "Default")
      (node (ref "A04") (pin "S1") (pinfunction "P$2_S1") (pintype "bidirectional"))
      (node (ref "B04") (pin "S1") (pinfunction "P$2_S1") (pintype "bidirectional"))
      (node (ref "B21") (pin "J2") (pinfunction "OUT_J2") (pintype "output"))
    )
    (net (code "31") (name "I_ADD09") (class "Default")
      (node (ref "A04") (pin "D2") (pinfunction "P$2_D2") (pintype "bidirectional"))
      (node (ref "B04") (pin "D2") (pinfunction "P$2_D2") (pintype "bidirectional"))
      (node (ref "B21") (pin "L2") (pinfunction "OUT_L2") (pintype "output"))
    )
    (net (code "32") (name "I_ADD10") (class "Default")
      (node (ref "A04") (pin "E2") (pinfunction "P$2_E2") (pintype "bidirectional"))
      (node (ref "B04") (pin "E2") (pinfunction "P$2_E2") (pintype "bidirectional"))
      (node (ref "B21") (pin "N2") (pinfunction "OUT_N2") (pintype "output"))
    )
    (net (code "33") (name "I_ADD11") (class "Default")
      (node (ref "A04") (pin "H2") (pinfunction "P$2_H2") (pintype "bidirectional"))
      (node (ref "B04") (pin "H2") (pinfunction "P$2_H2") (pintype "bidirectional"))
      (node (ref "B21") (pin "R2") (pinfunction "OUT_R2") (pintype "output"))
    )
    (net (code "34") (name "I_BAC00") (class "Default")
      (node (ref "A01") (pin "B1") (pinfunction "P$2_B1") (pintype "bidirectional"))
      (node (ref "B01") (pin "B1") (pinfunction "P$2_B1") (pintype "bidirectional"))
      (node (ref "B07") (pin "B1") (pinfunction "CATHODE_B1") (pintype "passive"))
      (node (ref "B10") (pin "H2") (pinfunction "IN2_H2") (pintype "input"))
    )
    (net (code "35") (name "I_BAC01") (class "Default")
      (node (ref "A01") (pin "D1") (pinfunction "P$2_D1") (pintype "bidirectional"))
      (node (ref "B01") (pin "D1") (pinfunction "P$2_D1") (pintype "bidirectional"))
      (node (ref "B07") (pin "D1") (pinfunction "CATHODE_D1") (pintype "passive"))
      (node (ref "B10") (pin "N2") (pinfunction "IN2_N2") (pintype "input"))
    )
    (net (code "36") (name "I_BAC02") (class "Default")
      (node (ref "A01") (pin "E1") (pinfunction "P$2_E1") (pintype "bidirectional"))
      (node (ref "B01") (pin "E1") (pinfunction "P$2_E1") (pintype "bidirectional"))
      (node (ref "B07") (pin "E1") (pinfunction "CATHODE_E1") (pintype "passive"))
      (node (ref "B10") (pin "U2") (pinfunction "IN2_U2") (pintype "input"))
    )
    (net (code "37") (name "I_BAC03") (class "Default")
      (node (ref "A01") (pin "H1") (pinfunction "P$2_H1") (pintype "bidirectional"))
      (node (ref "B01") (pin "H1") (pinfunction "P$2_H1") (pintype "bidirectional"))
      (node (ref "B07") (pin "H1") (pinfunction "CATHODE_H1") (pintype "passive"))
      (node (ref "B11") (pin "H2") (pinfunction "IN2_H2") (pintype "input"))
    )
    (net (code "38") (name "I_BAC04") (class "Default")
      (node (ref "A01") (pin "J1") (pinfunction "P$2_J1") (pintype "bidirectional"))
      (node (ref "B01") (pin "J1") (pinfunction "P$2_J1") (pintype "bidirectional"))
      (node (ref "B07") (pin "J1") (pinfunction "CATHODE_J1") (pintype "passive"))
      (node (ref "B11") (pin "N2") (pinfunction "IN2_N2") (pintype "input"))
    )
    (net (code "39") (name "I_BAC05") (class "Default")
      (node (ref "A01") (pin "L1") (pinfunction "P$2_L1") (pintype "bidirectional"))
      (node (ref "B01") (pin "L1") (pinfunction "P$2_L1") (pintype "bidirectional"))
      (node (ref "B07") (pin "L1") (pinfunction "CATHODE_L1") (pintype "passive"))
      (node (ref "B11") (pin "U2") (pinfunction "IN2_U2") (pintype "input"))
    )
    (net (code "40") (name "I_BAC06") (class "Default")
      (node (ref "A01") (pin "M1") (pinfunction "P$2_M1") (pintype "bidirectional"))
      (node (ref "B01") (pin "M1") (pinfunction "P$2_M1") (pintype "bidirectional"))
      (node (ref "B07") (pin "M1") (pinfunction "CATHODE_M1") (pintype "passive"))
      (node (ref "B12") (pin "H2") (pinfunction "IN2_H2") (pintype "input"))
    )
    (net (code "41") (name "I_BAC07") (class "Default")
      (node (ref "A01") (pin "P1") (pinfunction "P$2_P1") (pintype "bidirectional"))
      (node (ref "B01") (pin "P1") (pinfunction "P$2_P1") (pintype "bidirectional"))
      (node (ref "B07") (pin "P1") (pinfunction "CATHODE_P1") (pintype "passive"))
      (node (ref "B12") (pin "N2") (pinfunction "IN2_N2") (pintype "input"))
    )
    (net (code "42") (name "I_BAC08") (class "Default")
      (node (ref "A01") (pin "S1") (pinfunction "P$2_S1") (pintype "bidirectional"))
      (node (ref "B01") (pin "S1") (pinfunction "P$2_S1") (pintype "bidirectional"))
      (node (ref "B07") (pin "S1") (pinfunction "CATHODE_S1") (pintype "passive"))
      (node (ref "B12") (pin "U2") (pinfunction "IN2_U2") (pintype "input"))
    )
    (net (code "43") (name "I_BAC09") (class "Default")
      (node (ref "A01") (pin "D2") (pinfunction "P$2_D2") (pintype "bidirectional"))
      (node (ref "B01") (pin "D2") (pinfunction "P$2_D2") (pintype "bidirectional"))
      (node (ref "B07") (pin "D2") (pinfunction "CATHODE_D2") (pintype "passive"))
      (node (ref "B13") (pin "H2") (pinfunction "IN2_H2") (pintype "input"))
    )
    (net (code "44") (name "I_BAC10") (class "Default")
      (node (ref "A01") (pin "E2") (pinfunction "P$2_E2") (pintype "bidirectional"))
      (node (ref "B01") (pin "E2") (pinfunction "P$2_E2") (pintype "bidirectional"))
      (node (ref "B07") (pin "E2") (pinfunction "CATHODE_E2") (pintype "passive"))
      (node (ref "B13") (pin "N2") (pinfunction "IN2_N2") (pintype "input"))
    )
    (net (code "45") (name "I_BAC11") (class "Default")
      (node (ref "A01") (pin "H2") (pinfunction "P$2_H2") (pintype "bidirectional"))
      (node (ref "B01") (pin "H2") (pinfunction "P$2_H2") (pintype "bidirectional"))
      (node (ref "B07") (pin "H2") (pinfunction "CATHODE_H2") (pintype "passive"))
      (node (ref "B13") (pin "U2") (pinfunction "IN2_U2") (pintype "input"))
    )
    (net (code "46") (name "I_BREAK") (class "Default")
      (node (ref "A04") (pin "P2") (pinfunction "P$2_P2") (pintype "bidirectional"))
      (node (ref "B04") (pin "P2") (pinfunction "P$2_P2") (pintype "bidirectional"))
      (node (ref "B07") (pin "P2") (pinfunction "CATHODE_P2") (pintype "passive"))
      (node (ref "B14") (pin "U2") (pinfunction "IN2_U2") (pintype "input"))
      (node (ref "B22") (pin "V2") (pinfunction "P$1_V2") (pintype "input"))
      (node (ref "B23") (pin "V2") (pinfunction "P$1_V2") (pintype "input"))
    )
    (net (code "47") (name "I_BRKRQ") (class "Default")
      (node (ref "A04") (pin "K2") (pinfunction "P$2_K2") (pintype "bidirectional"))
      (node (ref "B04") (pin "K2") (pinfunction "P$2_K2") (pintype "bidirectional"))
      (node (ref "B18") (pin "N2") (pinfunction "OUT_N2") (pintype "output"))
    )
    (net (code "48") (name "I_CAINCR") (class "Default")
      (node (ref "A05") (pin "M2") (pinfunction "P$2_M2") (pintype "bidirectional"))
      (node (ref "B05") (pin "M2") (pinfunction "P$2_M2") (pintype "bidirectional"))
      (node (ref "B19") (pin "J2") (pinfunction "OUT_J2") (pintype "output"))
    )
    (net (code "49") (name "I_DATA00") (class "Default")
      (node (ref "A05") (pin "B1") (pinfunction "P$2_B1") (pintype "bidirectional"))
      (node (ref "B05") (pin "B1") (pinfunction "P$2_B1") (pintype "bidirectional"))
      (node (ref "B22") (pin "D2") (pinfunction "OUT_D2") (pintype "output"))
    )
    (net (code "50") (name "I_DATA01") (class "Default")
      (node (ref "A05") (pin "D1") (pinfunction "P$2_D1") (pintype "bidirectional"))
      (node (ref "B05") (pin "D1") (pinfunction "P$2_D1") (pintype "bidirectional"))
      (node (ref "B22") (pin "F2") (pinfunction "OUT_F2") (pintype "output"))
    )
    (net (code "51") (name "I_DATA02") (class "Default")
      (node (ref "A05") (pin "E1") (pinfunction "P$2_E1") (pintype "bidirectional"))
      (node (ref "B05") (pin "E1") (pinfunction "P$2_E1") (pintype "bidirectional"))
      (node (ref "B22") (pin "J2") (pinfunction "OUT_J2") (pintype "output"))
    )
    (net (code "52") (name "I_DATA03") (class "Default")
      (node (ref "A05") (pin "H1") (pinfunction "P$2_H1") (pintype "bidirectional"))
      (node (ref "B05") (pin "H1") (pinfunction "P$2_H1") (pintype "bidirectional"))
      (node (ref "B22") (pin "L2") (pinfunction "OUT_L2") (pintype "output"))
    )
    (net (code "53") (name "I_DATA04") (class "Default")
      (node (ref "A05") (pin "J1") (pinfunction "P$2_J1") (pintype "bidirectional"))
      (node (ref "B05") (pin "J1") (pinfunction "P$2_J1") (pintype "bidirectional"))
      (node (ref "B22") (pin "N2") (pinfunction "OUT_N2") (pintype "output"))
    )
    (net (code "54") (name "I_DATA05") (class "Default")
      (node (ref "A05") (pin "L1") (pinfunction "P$2_L1") (pintype "bidirectional"))
      (node (ref "B05") (pin "L1") (pinfunction "P$2_L1") (pintype "bidirectional"))
      (node (ref "B22") (pin "R2") (pinfunction "OUT_R2") (pintype "output"))
    )
    (net (code "55") (name "I_DATA06") (class "Default")
      (node (ref "A05") (pin "M1") (pinfunction "P$2_M1") (pintype "bidirectional"))
      (node (ref "B05") (pin "M1") (pinfunction "P$2_M1") (pintype "bidirectional"))
      (node (ref "B23") (pin "D2") (pinfunction "OUT_D2") (pintype "output"))
    )
    (net (code "56") (name "I_DATA07") (class "Default")
      (node (ref "A05") (pin "P1") (pinfunction "P$2_P1") (pintype "bidirectional"))
      (node (ref "B05") (pin "P1") (pinfunction "P$2_P1") (pintype "bidirectional"))
      (node (ref "B23") (pin "F2") (pinfunction "OUT_F2") (pintype "output"))
    )
    (net (code "57") (name "I_DATA08") (class "Default")
      (node (ref "A05") (pin "S1") (pinfunction "P$2_S1") (pintype "bidirectional"))
      (node (ref "B05") (pin "S1") (pinfunction "P$2_S1") (pintype "bidirectional"))
      (node (ref "B23") (pin "J2") (pinfunction "OUT_J2") (pintype "output"))
    )
    (net (code "58") (name "I_DATA09") (class "Default")
      (node (ref "A05") (pin "D2") (pinfunction "P$2_D2") (pintype "bidirectional"))
      (node (ref "B05") (pin "D2") (pinfunction "P$2_D2") (pintype "bidirectional"))
      (node (ref "B23") (pin "L2") (pinfunction "OUT_L2") (pintype "output"))
    )
    (net (code "59") (name "I_DATA10") (class "Default")
      (node (ref "A05") (pin "E2") (pinfunction "P$2_E2") (pintype "bidirectional"))
      (node (ref "B05") (pin "E2") (pinfunction "P$2_E2") (pintype "bidirectional"))
      (node (ref "B23") (pin "N2") (pinfunction "OUT_N2") (pintype "output"))
    )
    (net (code "60") (name "I_DATA11") (class "Default")
      (node (ref "A05") (pin "H2") (pinfunction "P$2_H2") (pintype "bidirectional"))
      (node (ref "B05") (pin "H2") (pinfunction "P$2_H2") (pintype "bidirectional"))
      (node (ref "B23") (pin "R2") (pinfunction "OUT_R2") (pintype "output"))
    )
    (net (code "61") (name "I_DATAIN") (class "Default")
      (node (ref "A04") (pin "M2") (pinfunction "P$2_M2") (pintype "bidirectional"))
      (node (ref "B04") (pin "M2") (pinfunction "P$2_M2") (pintype "bidirectional"))
      (node (ref "B18") (pin "R2") (pinfunction "OUT_R2") (pintype "output"))
    )
    (net (code "62") (name "I_EXTA0") (class "Default")
      (node (ref "A05") (pin "V2") (pinfunction "P$2_V2") (pintype "bidirectional"))
      (node (ref "B05") (pin "V2") (pinfunction "P$2_V2") (pintype "bidirectional"))
      (node (ref "B19") (pin "R2") (pinfunction "OUT_R2") (pintype "output"))
    )
    (net (code "63") (name "I_EXTA1") (class "Default")
      (node (ref "A05") (pin "T2") (pinfunction "P$2_T2") (pintype "bidirectional"))
      (node (ref "B05") (pin "T2") (pinfunction "P$2_T2") (pintype "bidirectional"))
      (node (ref "B19") (pin "N2") (pinfunction "OUT_N2") (pintype "output"))
    )
    (net (code "64") (name "I_EXTA2") (class "Default")
      (node (ref "A05") (pin "S2") (pinfunction "P$2_S2") (pintype "bidirectional"))
      (node (ref "B05") (pin "S2") (pinfunction "P$2_S2") (pintype "bidirectional"))
      (node (ref "B19") (pin "L2") (pinfunction "OUT_L2") (pintype "output"))
    )
    (net (code "65") (name "I_INIT") (class "Default")
      (node (ref "A01") (pin "V2") (pinfunction "P$2_V2") (pintype "bidirectional"))
      (node (ref "A04") (pin "V2") (pinfunction "P$2_V2") (pintype "bidirectional"))
      (node (ref "B01") (pin "V2") (pinfunction "P$2_V2") (pintype "bidirectional"))
      (node (ref "B04") (pin "V2") (pinfunction "P$2_V2") (pintype "bidirectional"))
      (node (ref "B06") (pin "N1") (pinfunction "IN_N1") (pintype "input"))
    )
    (net (code "66") (name "I_IOP1") (class "Default")
      (node (ref "A01") (pin "K2") (pinfunction "P$2_K2") (pintype "bidirectional"))
      (node (ref "B01") (pin "K2") (pinfunction "P$2_K2") (pintype "bidirectional"))
      (node (ref "B06") (pin "A1") (pinfunction "IN1_A1") (pintype "input"))
    )
    (net (code "67") (name "I_IOP2") (class "Default")
      (node (ref "A01") (pin "M2") (pinfunction "P$2_M2") (pintype "bidirectional"))
      (node (ref "B01") (pin "M2") (pinfunction "P$2_M2") (pintype "bidirectional"))
      (node (ref "B06") (pin "D1") (pinfunction "IN_D1") (pintype "input"))
    )
    (net (code "68") (name "I_IOP4") (class "Default")
      (node (ref "A01") (pin "P2") (pinfunction "P$2_P2") (pintype "bidirectional"))
      (node (ref "B01") (pin "P2") (pinfunction "P$2_P2") (pintype "bidirectional"))
      (node (ref "B06") (pin "F1") (pinfunction "IN_F1") (pintype "input"))
    )
    (net (code "69") (name "I_IRQ") (class "Default")
      (node (ref "A03") (pin "M2") (pinfunction "P$2_M2") (pintype "bidirectional"))
      (node (ref "B03") (pin "M2") (pinfunction "P$2_M2") (pintype "bidirectional"))
      (node (ref "B18") (pin "F2") (pinfunction "OUT_F2") (pintype "output"))
    )
    (net (code "70") (name "I_LINE") (class "Default")
      (node (ref "A03") (pin "V2") (pinfunction "P$2_V2") (pintype "bidirectional"))
      (node (ref "B03") (pin "V2") (pinfunction "P$2_V2") (pintype "bidirectional"))
      (node (ref "B18") (pin "L2") (pinfunction "OUT_L2") (pintype "output"))
    )
    (net (code "71") (name "I_MB00") (class "Default")
      (node (ref "A02") (pin "B1") (pinfunction "P$2_B1") (pintype "bidirectional"))
      (node (ref "A06") (pin "B1") (pinfunction "CATHODE_B1") (pintype "passive"))
      (node (ref "A07") (pin "H2") (pinfunction "IN2_H2") (pintype "input"))
      (node (ref "B02") (pin "B1") (pinfunction "P$2_B1") (pintype "bidirectional"))
    )
    (net (code "72") (name "I_MB01") (class "Default")
      (node (ref "A02") (pin "D1") (pinfunction "P$2_D1") (pintype "bidirectional"))
      (node (ref "A06") (pin "D1") (pinfunction "CATHODE_D1") (pintype "passive"))
      (node (ref "A07") (pin "N2") (pinfunction "IN2_N2") (pintype "input"))
      (node (ref "B02") (pin "D1") (pinfunction "P$2_D1") (pintype "bidirectional"))
    )
    (net (code "73") (name "I_MB02") (class "Default")
      (node (ref "A02") (pin "E1") (pinfunction "P$2_E1") (pintype "bidirectional"))
      (node (ref "A06") (pin "E1") (pinfunction "CATHODE_E1") (pintype "passive"))
      (node (ref "A07") (pin "U2") (pinfunction "IN2_U2") (pintype "input"))
      (node (ref "B02") (pin "E1") (pinfunction "P$2_E1") (pintype "bidirectional"))
    )
    (net (code "74") (name "I_MB03") (class "Default")
      (node (ref "A02") (pin "J1") (pinfunction "P$2_J1") (pintype "bidirectional"))
      (node (ref "A06") (pin "J1") (pinfunction "CATHODE_J1") (pintype "passive"))
      (node (ref "A08") (pin "N2") (pinfunction "IN2_N2") (pintype "input"))
      (node (ref "B02") (pin "J1") (pinfunction "P$2_J1") (pintype "bidirectional"))
    )
    (net (code "75") (name "I_MB04") (class "Default")
      (node (ref "A02") (pin "M1") (pinfunction "P$2_M1") (pintype "bidirectional"))
      (node (ref "A06") (pin "M1") (pinfunction "CATHODE_M1") (pintype "passive"))
      (node (ref "A09") (pin "H2") (pinfunction "IN2_H2") (pintype "input"))
      (node (ref "B02") (pin "M1") (pinfunction "P$2_M1") (pintype "bidirectional"))
    )
    (net (code "76") (name "I_MB05") (class "Default")
      (node (ref "A02") (pin "S1") (pinfunction "P$2_S1") (pintype "bidirectional"))
      (node (ref "A06") (pin "S1") (pinfunction "CATHODE_S1") (pintype "passive"))
      (node (ref "A09") (pin "U2") (pinfunction "IN2_U2") (pintype "input"))
      (node (ref "B02") (pin "S1") (pinfunction "P$2_S1") (pintype "bidirectional"))
    )
    (net (code "77") (name "I_MB06") (class "Default")
      (node (ref "A02") (pin "E2") (pinfunction "P$2_E2") (pintype "bidirectional"))
      (node (ref "A06") (pin "E2") (pinfunction "CATHODE_E2") (pintype "passive"))
      (node (ref "A10") (pin "N2") (pinfunction "IN2_N2") (pintype "input"))
      (node (ref "B02") (pin "E2") (pinfunction "P$2_E2") (pintype "bidirectional"))
    )
    (net (code "78") (name "I_MB07") (class "Default")
      (node (ref "A02") (pin "K2") (pinfunction "P$2_K2") (pintype "bidirectional"))
      (node (ref "A06") (pin "K2") (pinfunction "CATHODE_K2") (pintype "passive"))
      (node (ref "A11") (pin "H2") (pinfunction "IN2_H2") (pintype "input"))
      (node (ref "B02") (pin "K2") (pinfunction "P$2_K2") (pintype "bidirectional"))
    )
    (net (code "79") (name "I_MB08") (class "Default")
      (node (ref "A02") (pin "P2") (pinfunction "P$2_P2") (pintype "bidirectional"))
      (node (ref "A06") (pin "P2") (pinfunction "CATHODE_P2") (pintype "passive"))
      (node (ref "A11") (pin "U2") (pinfunction "IN2_U2") (pintype "input"))
      (node (ref "B02") (pin "P2") (pinfunction "P$2_P2") (pintype "bidirectional"))
    )
    (net (code "80") (name "I_MB09") (class "Default")
      (node (ref "A02") (pin "S2") (pinfunction "P$2_S2") (pintype "bidirectional"))
      (node (ref "A06") (pin "S2") (pinfunction "CATHODE_S2") (pintype "passive"))
      (node (ref "A12") (pin "H2") (pinfunction "IN2_H2") (pintype "input"))
      (node (ref "B02") (pin "S2") (pinfunction "P$2_S2") (pintype "bidirectional"))
    )
    (net (code "81") (name "I_MB10") (class "Default")
      (node (ref "A02") (pin "T2") (pinfunction "P$2_T2") (pintype "bidirectional"))
      (node (ref "A06") (pin "T2") (pinfunction "CATHODE_T2") (pintype "passive"))
      (node (ref "A12") (pin "N2") (pinfunction "IN2_N2") (pintype "input"))
      (node (ref "B02") (pin "T2") (pinfunction "P$2_T2") (pintype "bidirectional"))
    )
    (net (code "82") (name "I_MB11") (class "Default")
      (node (ref "A02") (pin "V2") (pinfunction "P$2_V2") (pintype "bidirectional"))
      (node (ref "A06") (pin "V2") (pinfunction "CATHODE_V2") (pintype "passive"))
      (node (ref "A12") (pin "U2") (pinfunction "IN2_U2") (pintype "input"))
      (node (ref "B02") (pin "V2") (pinfunction "P$2_V2") (pintype "bidirectional"))
    )
    (net (code "83") (name "I_MBINCR") (class "Default")
      (node (ref "A04") (pin "T2") (pinfunction "P$2_T2") (pintype "bidirectional"))
      (node (ref "B04") (pin "T2") (pinfunction "P$2_T2") (pintype "bidirectional"))
      (node (ref "B19") (pin "D2") (pinfunction "OUT_D2") (pintype "output"))
    )
    (net (code "84") (name "I_RUN") (class "Default")
      (node (ref "A03") (pin "S2") (pinfunction "P$2_S2") (pintype "bidirectional"))
      (node (ref "B03") (pin "S2") (pinfunction "P$2_S2") (pintype "bidirectional"))
      (node (ref "B07") (pin "K2") (pinfunction "CATHODE_K2") (pintype "passive"))
      (node (ref "B14") (pin "H2") (pinfunction "IN2_H2") (pintype "input"))
    )
    (net (code "85") (name "I_SKIP") (class "Default")
      (node (ref "A03") (pin "K2") (pinfunction "P$2_K2") (pintype "bidirectional"))
      (node (ref "B03") (pin "K2") (pinfunction "P$2_K2") (pintype "bidirectional"))
      (node (ref "B18") (pin "D2") (pinfunction "OUT_D2") (pintype "output"))
    )
    (net (code "86") (name "I_TS1") (class "Default")
      (node (ref "A01") (pin "T2") (pinfunction "P$2_T2") (pintype "bidirectional"))
      (node (ref "B01") (pin "T2") (pinfunction "P$2_T2") (pintype "bidirectional"))
      (node (ref "B06") (pin "L1") (pinfunction "IN_L1") (pintype "input"))
    )
    (net (code "87") (name "I_TS3") (class "Default")
      (node (ref "A01") (pin "S2") (pinfunction "P$2_S2") (pintype "bidirectional"))
      (node (ref "B01") (pin "S2") (pinfunction "P$2_S2") (pintype "bidirectional"))
      (node (ref "B06") (pin "J1") (pinfunction "IN_J1") (pintype "input"))
    )
    (net (code "88") (name "I_TT_INST") (class "Default")
      (node (ref "A03") (pin "T2") (pinfunction "P$2_T2") (pintype "bidirectional"))
      (node (ref "B03") (pin "T2") (pinfunction "P$2_T2") (pintype "bidirectional"))
      (node (ref "B07") (pin "M2") (pinfunction "CATHODE_M2") (pintype "passive"))
      (node (ref "B14") (pin "N2") (pinfunction "IN2_N2") (pintype "input"))
    )
    (net (code "89") (name "I_WCOV") (class "Default")
      (node (ref "A05") (pin "P2") (pinfunction "P$2_P2") (pintype "bidirectional"))
      (node (ref "B05") (pin "P2") (pinfunction "P$2_P2") (pintype "bidirectional"))
      (node (ref "B07") (pin "T2") (pinfunction "CATHODE_T2") (pintype "passive"))
      (node (ref "B15") (pin "N2") (pinfunction "IN2_N2") (pintype "input"))
    )
    (net (code "90") (name "Net-(B06A-OUT)") (class "Default")
      (node (ref "B06") (pin "B1") (pinfunction "OUT_B1") (pintype "output"))
      (node (ref "B08") (pin "H2") (pinfunction "IN2_H2") (pintype "input"))
    )
    (net (code "91") (name "Net-(B06B-OUT)") (class "Default")
      (node (ref "B06") (pin "E1") (pinfunction "OUT_E1") (pintype "output"))
      (node (ref "B08") (pin "N2") (pinfunction "IN2_N2") (pintype "input"))
    )
    (net (code "92") (name "Net-(B06F-OUT)") (class "Default")
      (node (ref "B06") (pin "H1") (pinfunction "OUT_H1") (pintype "output"))
      (node (ref "B08") (pin "U2") (pinfunction "IN2_U2") (pintype "input"))
    )
    (net (code "93") (name "Net-(B06H-OUT)") (class "Default")
      (node (ref "B06") (pin "K1") (pinfunction "OUT_K1") (pintype "output"))
      (node (ref "B09") (pin "H2") (pinfunction "IN2_H2") (pintype "input"))
    )
    (net (code "94") (name "Net-(B06J-OUT)") (class "Default")
      (node (ref "B06") (pin "M1") (pinfunction "OUT_M1") (pintype "output"))
      (node (ref "B09") (pin "N2") (pinfunction "IN2_N2") (pintype "input"))
    )
    (net (code "95") (name "Net-(B06L-OUT)") (class "Default")
      (node (ref "B06") (pin "P1") (pinfunction "OUT_P1") (pintype "output"))
      (node (ref "B09") (pin "U2") (pinfunction "IN2_U2") (pintype "input"))
    )
    (net (code "96") (name "O_3CYCLE") (class "Default")
      (node (ref "A22") (pin "K2") (pinfunction "P$2_K2") (pintype "bidirectional"))
      (node (ref "B19") (pin "H2") (pinfunction "IN_H2") (pintype "input"))
    )
    (net (code "97") (name "O_AC00") (class "Default")
      (node (ref "A17") (pin "D2") (pinfunction "P$2_D2") (pintype "bidirectional"))
      (node (ref "B16") (pin "E2") (pinfunction "IN_E2") (pintype "input"))
    )
    (net (code "98") (name "O_AC01") (class "Default")
      (node (ref "A17") (pin "E2") (pinfunction "P$2_E2") (pintype "bidirectional"))
      (node (ref "B16") (pin "H2") (pinfunction "IN_H2") (pintype "input"))
    )
    (net (code "99") (name "O_AC02") (class "Default")
      (node (ref "A17") (pin "H2") (pinfunction "P$2_H2") (pintype "bidirectional"))
      (node (ref "B16") (pin "K2") (pinfunction "IN_K2") (pintype "input"))
    )
    (net (code "100") (name "O_AC03") (class "Default")
      (node (ref "A17") (pin "K2") (pinfunction "P$2_K2") (pintype "bidirectional"))
      (node (ref "B16") (pin "M2") (pinfunction "IN_M2") (pintype "input"))
    )
    (net (code "101") (name "O_AC04") (class "Default")
      (node (ref "A17") (pin "M2") (pinfunction "P$2_M2") (pintype "bidirectional"))
      (node (ref "B16") (pin "P2") (pinfunction "IN_P2") (pintype "input"))
    )
    (net (code "102") (name "O_AC05") (class "Default")
      (node (ref "A17") (pin "P2") (pinfunction "P$2_P2") (pintype "bidirectional"))
      (node (ref "B16") (pin "S2") (pinfunction "IN_S2") (pintype "input"))
    )
    (net (code "103") (name "O_AC06") (class "Default")
      (node (ref "A17") (pin "S2") (pinfunction "P$2_S2") (pintype "bidirectional"))
      (node (ref "B17") (pin "E2") (pinfunction "IN_E2") (pintype "input"))
    )
    (net (code "104") (name "O_AC07") (class "Default")
      (node (ref "A17") (pin "T2") (pinfunction "P$2_T2") (pintype "bidirectional"))
      (node (ref "B17") (pin "H2") (pinfunction "IN_H2") (pintype "input"))
    )
    (net (code "105") (name "O_AC08") (class "Default")
      (node (ref "A17") (pin "V2") (pinfunction "P$2_V2") (pintype "bidirectional"))
      (node (ref "B17") (pin "K2") (pinfunction "IN_K2") (pintype "input"))
    )
    (net (code "106") (name "O_AC09") (class "Default")
      (node (ref "A18") (pin "D2") (pinfunction "P$2_D2") (pintype "bidirectional"))
      (node (ref "B17") (pin "M2") (pinfunction "IN_M2") (pintype "input"))
    )
    (net (code "107") (name "O_AC10") (class "Default")
      (node (ref "A18") (pin "E2") (pinfunction "P$2_E2") (pintype "bidirectional"))
      (node (ref "B17") (pin "P2") (pinfunction "IN_P2") (pintype "input"))
    )
    (net (code "108") (name "O_AC11") (class "Default")
      (node (ref "A18") (pin "H2") (pinfunction "P$2_H2") (pintype "bidirectional"))
      (node (ref "B17") (pin "S2") (pinfunction "IN_S2") (pintype "input"))
    )
    (net (code "109") (name "O_ACCEPT") (class "Default")
      (node (ref "A20") (pin "S2") (pinfunction "P$2_S2") (pintype "bidirectional"))
      (node (ref "B15") (pin "D2") (pinfunction "OUT_D2") (pintype "output"))
    )
    (net (code "110") (name "O_ACCLR") (class "Default")
      (node (ref "A18") (pin "P2") (pinfunction "P$2_P2") (pintype "bidirectional"))
      (node (ref "B18") (pin "K2") (pinfunction "IN_K2") (pintype "input"))
    )
    (net (code "111") (name "O_ADD00") (class "Default")
      (node (ref "A19") (pin "D2") (pinfunction "P$2_D2") (pintype "bidirectional"))
      (node (ref "B20") (pin "E2") (pinfunction "IN_E2") (pintype "input"))
    )
    (net (code "112") (name "O_ADD01") (class "Default")
      (node (ref "A19") (pin "E2") (pinfunction "P$2_E2") (pintype "bidirectional"))
      (node (ref "B20") (pin "H2") (pinfunction "IN_H2") (pintype "input"))
    )
    (net (code "113") (name "O_ADD02") (class "Default")
      (node (ref "A19") (pin "H2") (pinfunction "P$2_H2") (pintype "bidirectional"))
      (node (ref "B20") (pin "K2") (pinfunction "IN_K2") (pintype "input"))
    )
    (net (code "114") (name "O_ADD03") (class "Default")
      (node (ref "A19") (pin "K2") (pinfunction "P$2_K2") (pintype "bidirectional"))
      (node (ref "B20") (pin "M2") (pinfunction "IN_M2") (pintype "input"))
    )
    (net (code "115") (name "O_ADD04") (class "Default")
      (node (ref "A19") (pin "M2") (pinfunction "P$2_M2") (pintype "bidirectional"))
      (node (ref "B20") (pin "P2") (pinfunction "IN_P2") (pintype "input"))
    )
    (net (code "116") (name "O_ADD05") (class "Default")
      (node (ref "A19") (pin "P2") (pinfunction "P$2_P2") (pintype "bidirectional"))
      (node (ref "B20") (pin "S2") (pinfunction "IN_S2") (pintype "input"))
    )
    (net (code "117") (name "O_ADD06") (class "Default")
      (node (ref "A19") (pin "S2") (pinfunction "P$2_S2") (pintype "bidirectional"))
      (node (ref "B21") (pin "E2") (pinfunction "IN_E2") (pintype "input"))
    )
    (net (code "118") (name "O_ADD07") (class "Default")
      (node (ref "A19") (pin "T2") (pinfunction "P$2_T2") (pintype "bidirectional"))
      (node (ref "B21") (pin "H2") (pinfunction "IN_H2") (pintype "input"))
    )
    (net (code "119") (name "O_ADD08") (class "Default")
      (node (ref "A19") (pin "V2") (pinfunction "P$2_V2") (pintype "bidirectional"))
      (node (ref "B21") (pin "K2") (pinfunction "IN_K2") (pintype "input"))
    )
    (net (code "120") (name "O_ADD09") (class "Default")
      (node (ref "A20") (pin "D2") (pinfunction "P$2_D2") (pintype "bidirectional"))
      (node (ref "B21") (pin "M2") (pinfunction "IN_M2") (pintype "input"))
    )
    (net (code "121") (name "O_ADD10") (class "Default")
      (node (ref "A20") (pin "E2") (pinfunction "P$2_E2") (pintype "bidirectional"))
      (node (ref "B21") (pin "P2") (pinfunction "IN_P2") (pintype "input"))
    )
    (net (code "122") (name "O_ADD11") (class "Default")
      (node (ref "A20") (pin "H2") (pinfunction "P$2_H2") (pintype "bidirectional"))
      (node (ref "B21") (pin "S2") (pinfunction "IN_S2") (pintype "input"))
    )
    (net (code "123") (name "O_BAC00") (class "Default")
      (node (ref "A13") (pin "D2") (pinfunction "P$2_D2") (pintype "bidirectional"))
      (node (ref "B10") (pin "D2") (pinfunction "OUT_D2") (pintype "output"))
    )
    (net (code "124") (name "O_BAC01") (class "Default")
      (node (ref "A13") (pin "E2") (pinfunction "P$2_E2") (pintype "bidirectional"))
      (node (ref "B10") (pin "K2") (pinfunction "OUT_K2") (pintype "output"))
    )
    (net (code "125") (name "O_BAC02") (class "Default")
      (node (ref "A13") (pin "H2") (pinfunction "P$2_H2") (pintype "bidirectional"))
      (node (ref "B10") (pin "S2") (pinfunction "OUT_S2") (pintype "output"))
    )
    (net (code "126") (name "O_BAC03") (class "Default")
      (node (ref "A13") (pin "K2") (pinfunction "P$2_K2") (pintype "bidirectional"))
      (node (ref "B11") (pin "D2") (pinfunction "OUT_D2") (pintype "output"))
    )
    (net (code "127") (name "O_BAC04") (class "Default")
      (node (ref "A13") (pin "M2") (pinfunction "P$2_M2") (pintype "bidirectional"))
      (node (ref "B11") (pin "K2") (pinfunction "OUT_K2") (pintype "output"))
    )
    (net (code "128") (name "O_BAC05") (class "Default")
      (node (ref "A13") (pin "P2") (pinfunction "P$2_P2") (pintype "bidirectional"))
      (node (ref "B11") (pin "S2") (pinfunction "OUT_S2") (pintype "output"))
    )
    (net (code "129") (name "O_BAC06") (class "Default")
      (node (ref "A13") (pin "S2") (pinfunction "P$2_S2") (pintype "bidirectional"))
      (node (ref "B12") (pin "D2") (pinfunction "OUT_D2") (pintype "output"))
    )
    (net (code "130") (name "O_BAC07") (class "Default")
      (node (ref "A13") (pin "T2") (pinfunction "P$2_T2") (pintype "bidirectional"))
      (node (ref "B12") (pin "K2") (pinfunction "OUT_K2") (pintype "output"))
    )
    (net (code "131") (name "O_BAC08") (class "Default")
      (node (ref "A13") (pin "V2") (pinfunction "P$2_V2") (pintype "bidirectional"))
      (node (ref "B12") (pin "S2") (pinfunction "OUT_S2") (pintype "output"))
    )
    (net (code "132") (name "O_BAC09") (class "Default")
      (node (ref "A14") (pin "D2") (pinfunction "P$2_D2") (pintype "bidirectional"))
      (node (ref "B13") (pin "D2") (pinfunction "OUT_D2") (pintype "output"))
    )
    (net (code "133") (name "O_BAC10") (class "Default")
      (node (ref "A14") (pin "E2") (pinfunction "P$2_E2") (pintype "bidirectional"))
      (node (ref "B13") (pin "K2") (pinfunction "OUT_K2") (pintype "output"))
    )
    (net (code "134") (name "O_BAC11") (class "Default")
      (node (ref "A14") (pin "H2") (pinfunction "P$2_H2") (pintype "bidirectional"))
      (node (ref "B13") (pin "S2") (pinfunction "OUT_S2") (pintype "output"))
    )
    (net (code "135") (name "O_BREAK") (class "Default")
      (node (ref "A20") (pin "P2") (pinfunction "P$2_P2") (pintype "bidirectional"))
      (node (ref "B14") (pin "S2") (pinfunction "OUT_S2") (pintype "output"))
    )
    (net (code "136") (name "O_BRKRQ") (class "Default")
      (node (ref "A20") (pin "K2") (pinfunction "P$2_K2") (pintype "bidirectional"))
      (node (ref "B18") (pin "P2") (pinfunction "IN_P2") (pintype "input"))
    )
    (net (code "137") (name "O_CAINCR") (class "Default")
      (node (ref "A22") (pin "M2") (pinfunction "P$2_M2") (pintype "bidirectional"))
      (node (ref "B19") (pin "K2") (pinfunction "IN_K2") (pintype "input"))
    )
    (net (code "138") (name "O_DATA00") (class "Default")
      (node (ref "A21") (pin "D2") (pinfunction "P$2_D2") (pintype "bidirectional"))
      (node (ref "B22") (pin "E2") (pinfunction "IN_E2") (pintype "input"))
    )
    (net (code "139") (name "O_DATA01") (class "Default")
      (node (ref "A21") (pin "E2") (pinfunction "P$2_E2") (pintype "bidirectional"))
      (node (ref "B22") (pin "H2") (pinfunction "IN_H2") (pintype "input"))
    )
    (net (code "140") (name "O_DATA02") (class "Default")
      (node (ref "A21") (pin "H2") (pinfunction "P$2_H2") (pintype "bidirectional"))
      (node (ref "B22") (pin "K2") (pinfunction "IN_K2") (pintype "input"))
    )
    (net (code "141") (name "O_DATA03") (class "Default")
      (node (ref "A21") (pin "K2") (pinfunction "P$2_K2") (pintype "bidirectional"))
      (node (ref "B22") (pin "M2") (pinfunction "IN_M2") (pintype "input"))
    )
    (net (code "142") (name "O_DATA04") (class "Default")
      (node (ref "A21") (pin "M2") (pinfunction "P$2_M2") (pintype "bidirectional"))
      (node (ref "B22") (pin "P2") (pinfunction "IN_P2") (pintype "input"))
    )
    (net (code "143") (name "O_DATA05") (class "Default")
      (node (ref "A21") (pin "P2") (pinfunction "P$2_P2") (pintype "bidirectional"))
      (node (ref "B22") (pin "S2") (pinfunction "IN_S2") (pintype "input"))
    )
    (net (code "144") (name "O_DATA06") (class "Default")
      (node (ref "A21") (pin "S2") (pinfunction "P$2_S2") (pintype "bidirectional"))
      (node (ref "B23") (pin "E2") (pinfunction "IN_E2") (pintype "input"))
    )
    (net (code "145") (name "O_DATA07") (class "Default")
      (node (ref "A21") (pin "T2") (pinfunction "P$2_T2") (pintype "bidirectional"))
      (node (ref "B23") (pin "H2") (pinfunction "IN_H2") (pintype "input"))
    )
    (net (code "146") (name "O_DATA08") (class "Default")
      (node (ref "A21") (pin "V2") (pinfunction "P$2_V2") (pintype "bidirectional"))
      (node (ref "B23") (pin "K2") (pinfunction "IN_K2") (pintype "input"))
    )
    (net (code "147") (name "O_DATA09") (class "Default")
      (node (ref "A22") (pin "D2") (pinfunction "P$2_D2") (pintype "bidirectional"))
      (node (ref "B23") (pin "M2") (pinfunction "IN_M2") (pintype "input"))
    )
    (net (code "148") (name "O_DATA10") (class "Default")
      (node (ref "A22") (pin "E2") (pinfunction "P$2_E2") (pintype "bidirectional"))
      (node (ref "B23") (pin "P2") (pinfunction "IN_P2") (pintype "input"))
    )
    (net (code "149") (name "O_DATA11") (class "Default")
      (node (ref "A22") (pin "H2") (pinfunction "P$2_H2") (pintype "bidirectional"))
      (node (ref "B23") (pin "S2") (pinfunction "IN_S2") (pintype "input"))
    )
    (net (code "150") (name "O_DATAIN") (class "Default")
      (node (ref "A20") (pin "M2") (pinfunction "P$2_M2") (pintype "bidirectional"))
      (node (ref "B18") (pin "S2") (pinfunction "IN_S2") (pintype "input"))
    )
    (net (code "151") (name "O_EXTA0") (class "Default")
      (node (ref "A23") (pin "H2") (pinfunction "P$2_H2") (pintype "bidirectional"))
      (node (ref "B19") (pin "S2") (pinfunction "IN_S2") (pintype "input"))
    )
    (net (code "152") (name "O_EXTA1") (class "Default")
      (node (ref "A23") (pin "E2") (pinfunction "P$2_E2") (pintype "bidirectional"))
      (node (ref "B19") (pin "P2") (pinfunction "IN_P2") (pintype "input"))
    )
    (net (code "153") (name "O_EXTA2") (class "Default")
      (node (ref "A23") (pin "D2") (pinfunction "P$2_D2") (pintype "bidirectional"))
      (node (ref "B19") (pin "M2") (pinfunction "IN_M2") (pintype "input"))
    )
    (net (code "154") (name "O_INIT") (class "Default")
      (node (ref "A14") (pin "V2") (pinfunction "P$2_V2") (pintype "bidirectional"))
      (node (ref "B09") (pin "S2") (pinfunction "OUT_S2") (pintype "output"))
    )
    (net (code "155") (name "O_IOP1") (class "Default")
      (node (ref "A14") (pin "K2") (pinfunction "P$2_K2") (pintype "bidirectional"))
      (node (ref "B08") (pin "D2") (pinfunction "OUT_D2") (pintype "output"))
    )
    (net (code "156") (name "O_IOP2") (class "Default")
      (node (ref "A14") (pin "M2") (pinfunction "P$2_M2") (pintype "bidirectional"))
      (node (ref "B08") (pin "K2") (pinfunction "OUT_K2") (pintype "output"))
    )
    (net (code "157") (name "O_IOP4") (class "Default")
      (node (ref "A14") (pin "P2") (pinfunction "P$2_P2") (pintype "bidirectional"))
      (node (ref "B08") (pin "S2") (pinfunction "OUT_S2") (pintype "output"))
    )
    (net (code "158") (name "O_IRQ") (class "Default")
      (node (ref "A18") (pin "M2") (pinfunction "P$2_M2") (pintype "bidirectional"))
      (node (ref "B18") (pin "H2") (pinfunction "IN_H2") (pintype "input"))
    )
    (net (code "159") (name "O_LINE") (class "Default")
      (node (ref "A18") (pin "V2") (pinfunction "P$2_V2") (pintype "bidirectional"))
      (node (ref "B18") (pin "M2") (pinfunction "IN_M2") (pintype "input"))
    )
    (net (code "160") (name "O_MB00") (class "Default")
      (node (ref "A07") (pin "D2") (pinfunction "OUT_D2") (pintype "output"))
      (node (ref "A15") (pin "D2") (pinfunction "P$2_D2") (pintype "bidirectional"))
    )
    (net (code "161") (name "O_MB01") (class "Default")
      (node (ref "A07") (pin "K2") (pinfunction "OUT_K2") (pintype "output"))
      (node (ref "A15") (pin "E2") (pinfunction "P$2_E2") (pintype "bidirectional"))
    )
    (net (code "162") (name "O_MB02") (class "Default")
      (node (ref "A07") (pin "S2") (pinfunction "OUT_S2") (pintype "output"))
      (node (ref "A15") (pin "H2") (pinfunction "P$2_H2") (pintype "bidirectional"))
    )
    (net (code "163") (name "O_MB03") (class "Default")
      (node (ref "A08") (pin "K2") (pinfunction "OUT_K2") (pintype "output"))
      (node (ref "A15") (pin "M2") (pinfunction "P$2_M2") (pintype "bidirectional"))
    )
    (net (code "164") (name "O_MB04") (class "Default")
      (node (ref "A09") (pin "D2") (pinfunction "OUT_D2") (pintype "output"))
      (node (ref "A15") (pin "S2") (pinfunction "P$2_S2") (pintype "bidirectional"))
    )
    (net (code "165") (name "O_MB05") (class "Default")
      (node (ref "A09") (pin "S2") (pinfunction "OUT_S2") (pintype "output"))
      (node (ref "A15") (pin "V2") (pinfunction "P$2_V2") (pintype "bidirectional"))
    )
    (net (code "166") (name "O_MB06") (class "Default")
      (node (ref "A10") (pin "K2") (pinfunction "OUT_K2") (pintype "output"))
      (node (ref "A16") (pin "E2") (pinfunction "P$2_E2") (pintype "bidirectional"))
    )
    (net (code "167") (name "O_MB07") (class "Default")
      (node (ref "A11") (pin "D2") (pinfunction "OUT_D2") (pintype "output"))
      (node (ref "A16") (pin "K2") (pinfunction "P$2_K2") (pintype "bidirectional"))
    )
    (net (code "168") (name "O_MB08") (class "Default")
      (node (ref "A11") (pin "S2") (pinfunction "OUT_S2") (pintype "output"))
      (node (ref "A16") (pin "P2") (pinfunction "P$2_P2") (pintype "bidirectional"))
    )
    (net (code "169") (name "O_MB09") (class "Default")
      (node (ref "A12") (pin "D2") (pinfunction "OUT_D2") (pintype "output"))
      (node (ref "A16") (pin "S2") (pinfunction "P$2_S2") (pintype "bidirectional"))
    )
    (net (code "170") (name "O_MB10") (class "Default")
      (node (ref "A12") (pin "K2") (pinfunction "OUT_K2") (pintype "output"))
      (node (ref "A16") (pin "T2") (pinfunction "P$2_T2") (pintype "bidirectional"))
    )
    (net (code "171") (name "O_MB11") (class "Default")
      (node (ref "A12") (pin "S2") (pinfunction "OUT_S2") (pintype "output"))
      (node (ref "A16") (pin "V2") (pinfunction "P$2_V2") (pintype "bidirectional"))
    )
    (net (code "172") (name "O_MBINCR") (class "Default")
      (node (ref "A20") (pin "T2") (pinfunction "P$2_T2") (pintype "bidirectional"))
      (node (ref "B19") (pin "E2") (pinfunction "IN_E2") (pintype "input"))
    )
    (net (code "173") (name "O_RUN") (class "Default")
      (node (ref "A18") (pin "S2") (pinfunction "P$2_S2") (pintype "bidirectional"))
      (node (ref "B14") (pin "D2") (pinfunction "OUT_D2") (pintype "output"))
    )
    (net (code "174") (name "O_SKIP") (class "Default")
      (node (ref "A18") (pin "K2") (pinfunction "P$2_K2") (pintype "bidirectional"))
      (node (ref "B18") (pin "E2") (pinfunction "IN_E2") (pintype "input"))
    )
    (net (code "175") (name "O_TS1") (class "Default")
      (node (ref "A14") (pin "T2") (pinfunction "P$2_T2") (pintype "bidirectional"))
      (node (ref "B09") (pin "K2") (pinfunction "OUT_K2") (pintype "output"))
    )
    (net (code "176") (name "O_TS3") (class "Default")
      (node (ref "A14") (pin "S2") (pinfunction "P$2_S2") (pintype "bidirectional"))
      (node (ref "B09") (pin "D2") (pinfunction "OUT_D2") (pintype "output"))
    )
    (net (code "177") (name "O_TT_INST") (class "Default")
      (node (ref "A18") (pin "T2") (pinfunction "P$2_T2") (pintype "bidirectional"))
      (node (ref "B14") (pin "K2") (pinfunction "OUT_K2") (pintype "output"))
    )
    (net (code "178") (name "O_WCOV") (class "Default")
      (node (ref "A22") (pin "P2") (pinfunction "P$2_P2") (pintype "bidirectional"))
      (node (ref "B15") (pin "K2") (pinfunction "OUT_K2") (pintype "output"))
    )
    (net (code "180") (name "unconnected-(A07A-SLOW-PadE2)") (class "Default")
      (node (ref "A07") (pin "E2") (pinfunction "SLOW_E2") (pintype "passive"))
    )
    (net (code "181") (name "unconnected-(A07D-SLOW-PadL2)") (class "Default")
      (node (ref "A07") (pin "L2") (pinfunction "SLOW_L2") (pintype "passive"))
    )
    (net (code "182") (name "unconnected-(A07E-SLOW-PadR2)") (class "Default")
      (node (ref "A07") (pin "R2") (pinfunction "SLOW_R2") (pintype "passive"))
    )
    (net (code "183") (name "unconnected-(A08A-SLOW-PadE2)") (class "Default")
      (node (ref "A08") (pin "E2") (pinfunction "SLOW_E2") (pintype "passive"))
    )
    (net (code "184") (name "unconnected-(A08D-SLOW-PadL2)") (class "Default")
      (node (ref "A08") (pin "L2") (pinfunction "SLOW_L2") (pintype "passive"))
    )
    (net (code "185") (name "unconnected-(A08E-SLOW-PadR2)") (class "Default")
      (node (ref "A08") (pin "R2") (pinfunction "SLOW_R2") (pintype "passive"))
    )
    (net (code "186") (name "unconnected-(A09A-SLOW-PadE2)") (class "Default")
      (node (ref "A09") (pin "E2") (pinfunction "SLOW_E2") (pintype "passive"))
    )
    (net (code "187") (name "unconnected-(A09D-SLOW-PadL2)") (class "Default")
      (node (ref "A09") (pin "L2") (pinfunction "SLOW_L2") (pintype "passive"))
    )
    (net (code "188") (name "unconnected-(A09E-SLOW-PadR2)") (class "Default")
      (node (ref "A09") (pin "R2") (pinfunction "SLOW_R2") (pintype "passive"))
    )
    (net (code "189") (name "unconnected-(A10A-SLOW-PadE2)") (class "Default")
      (node (ref "A10") (pin "E2") (pinfunction "SLOW_E2") (pintype "passive"))
    )
    (net (code "190") (name "unconnected-(A10D-SLOW-PadL2)") (class "Default")
      (node (ref "A10") (pin "L2") (pinfunction "SLOW_L2") (pintype "passive"))
    )
    (net (code "191") (name "unconnected-(A10E-SLOW-PadR2)") (class "Default")
      (node (ref "A10") (pin "R2") (pinfunction "SLOW_R2") (pintype "passive"))
    )
    (net (code "192") (name "unconnected-(A11A-SLOW-PadE2)") (class "Default")
      (node (ref "A11") (pin "E2") (pinfunction "SLOW_E2") (pintype "passive"))
    )
    (net (code "193") (name "unconnected-(A11D-SLOW-PadL2)") (class "Default")
      (node (ref "A11") (pin "L2") (pinfunction "SLOW_L2") (pintype "passive"))
    )
    (net (code "194") (name "unconnected-(A11E-SLOW-PadR2)") (class "Default")
      (node (ref "A11") (pin "R2") (pinfunction "SLOW_R2") (pintype "passive"))
    )
    (net (code "195") (name "unconnected-(A12A-SLOW-PadE2)") (class "Default")
      (node (ref "A12") (pin "E2") (pinfunction "SLOW_E2") (pintype "passive"))
    )
    (net (code "196") (name "unconnected-(A12D-SLOW-PadL2)") (class "Default")
      (node (ref "A12") (pin "L2") (pinfunction "SLOW_L2") (pintype "passive"))
    )
    (net (code "197") (name "unconnected-(A12E-SLOW-PadR2)") (class "Default")
      (node (ref "A12") (pin "R2") (pinfunction "SLOW_R2") (pintype "passive"))
    )
    (net (code "198") (name "unconnected-(B08A-SLOW-PadE2)") (class "Default")
      (node (ref "B08") (pin "E2") (pinfunction "SLOW_E2") (pintype "passive"))
    )
    (net (code "199") (name "unconnected-(B08D-SLOW-PadL2)") (class "Default")
      (node (ref "B08") (pin "L2") (pinfunction "SLOW_L2") (pintype "passive"))
    )
    (net (code "200") (name "unconnected-(B08E-SLOW-PadR2)") (class "Default")
      (node (ref "B08") (pin "R2") (pinfunction "SLOW_R2") (pintype "passive"))
    )
    (net (code "201") (name "unconnected-(B09A-SLOW-PadE2)") (class "Default")
      (node (ref "B09") (pin "E2") (pinfunction "SLOW_E2") (pintype "passive"))
    )
    (net (code "202") (name "unconnected-(B09D-SLOW-PadL2)") (class "Default")
      (node (ref "B09") (pin "L2") (pinfunction "SLOW_L2") (pintype "passive"))
    )
    (net (code "203") (name "unconnected-(B09E-SLOW-PadR2)") (class "Default")
      (node (ref "B09") (pin "R2") (pinfunction "SLOW_R2") (pintype "passive"))
    )
    (net (code "204") (name "unconnected-(B10A-SLOW-PadE2)") (class "Default")
      (node (ref "B10") (pin "E2") (pinfunction "SLOW_E2") (pintype "passive"))
    )
    (net (code "205") (name "unconnected-(B10D-SLOW-PadL2)") (class "Default")
      (node (ref "B10") (pin "L2") (pinfunction "SLOW_L2") (pintype "passive"))
    )
    (net (code "206") (name "unconnected-(B10E-SLOW-PadR2)") (class "Default")
      (node (ref "B10") (pin "R2") (pinfunction "SLOW_R2") (pintype "passive"))
    )
    (net (code "207") (name "unconnected-(B11A-SLOW-PadE2)") (class "Default")
      (node (ref "B11") (pin "E2") (pinfunction "SLOW_E2") (pintype "passive"))
    )
    (net (code "208") (name "unconnected-(B11D-SLOW-PadL2)") (class "Default")
      (node (ref "B11") (pin "L2") (pinfunction "SLOW_L2") (pintype "passive"))
    )
    (net (code "209") (name "unconnected-(B11E-SLOW-PadR2)") (class "Default")
      (node (ref "B11") (pin "R2") (pinfunction "SLOW_R2") (pintype "passive"))
    )
    (net (code "210") (name "unconnected-(B12A-SLOW-PadE2)") (class "Default")
      (node (ref "B12") (pin "E2") (pinfunction "SLOW_E2") (pintype "passive"))
    )
    (net (code "211") (name "unconnected-(B12D-SLOW-PadL2)") (class "Default")
      (node (ref "B12") (pin "L2") (pinfunction "SLOW_L2") (pintype "passive"))
    )
    (net (code "212") (name "unconnected-(B12E-SLOW-PadR2)") (class "Default")
      (node (ref "B12") (pin "R2") (pinfunction "SLOW_R2") (pintype "passive"))
    )
    (net (code "213") (name "unconnected-(B13A-SLOW-PadE2)") (class "Default")
      (node (ref "B13") (pin "E2") (pinfunction "SLOW_E2") (pintype "passive"))
    )
    (net (code "214") (name "unconnected-(B13D-SLOW-PadL2)") (class "Default")
      (node (ref "B13") (pin "L2") (pinfunction "SLOW_L2") (pintype "passive"))
    )
    (net (code "215") (name "unconnected-(B13E-SLOW-PadR2)") (class "Default")
      (node (ref "B13") (pin "R2") (pinfunction "SLOW_R2") (pintype "passive"))
    )
    (net (code "216") (name "unconnected-(B14A-SLOW-PadE2)") (class "Default")
      (node (ref "B14") (pin "E2") (pinfunction "SLOW_E2") (pintype "passive"))
    )
    (net (code "217") (name "unconnected-(B14D-SLOW-PadL2)") (class "Default")
      (node (ref "B14") (pin "L2") (pinfunction "SLOW_L2") (pintype "passive"))
    )
    (net (code "218") (name "unconnected-(B14E-SLOW-PadR2)") (class "Default")
      (node (ref "B14") (pin "R2") (pinfunction "SLOW_R2") (pintype "passive"))
    )
    (net (code "219") (name "unconnected-(B15A-SLOW-PadE2)") (class "Default")
      (node (ref "B15") (pin "E2") (pinfunction "SLOW_E2") (pintype "passive"))
    )
    (net (code "220") (name "unconnected-(B15D-SLOW-PadL2)") (class "Default")
      (node (ref "B15") (pin "L2") (pinfunction "SLOW_L2") (pintype "passive"))
    )
    (net (code "221") (name "~{I_MB03}") (class "Default")
      (node (ref "A02") (pin "H1") (pinfunction "P$2_H1") (pintype "bidirectional"))
      (node (ref "A06") (pin "H1") (pinfunction "CATHODE_H1") (pintype "passive"))
      (node (ref "A08") (pin "H2") (pinfunction "IN2_H2") (pintype "input"))
      (node (ref "B02") (pin "H1") (pinfunction "P$2_H1") (pintype "bidirectional"))
    )
    (net (code "222") (name "~{I_MB04}") (class "Default")
      (node (ref "A02") (pin "L1") (pinfunction "P$2_L1") (pintype "bidirectional"))
      (node (ref "A06") (pin "L1") (pinfunction "CATHODE_L1") (pintype "passive"))
      (node (ref "A08") (pin "U2") (pinfunction "IN2_U2") (pintype "input"))
      (node (ref "B02") (pin "L1") (pinfunction "P$2_L1") (pintype "bidirectional"))
    )
    (net (code "223") (name "~{I_MB05}") (class "Default")
      (node (ref "A02") (pin "P1") (pinfunction "P$2_P1") (pintype "bidirectional"))
      (node (ref "A06") (pin "P1") (pinfunction "CATHODE_P1") (pintype "passive"))
      (node (ref "A09") (pin "N2") (pinfunction "IN2_N2") (pintype "input"))
      (node (ref "B02") (pin "P1") (pinfunction "P$2_P1") (pintype "bidirectional"))
    )
    (net (code "224") (name "~{I_MB06}") (class "Default")
      (node (ref "A02") (pin "D2") (pinfunction "P$2_D2") (pintype "bidirectional"))
      (node (ref "A06") (pin "D2") (pinfunction "CATHODE_D2") (pintype "passive"))
      (node (ref "A10") (pin "H2") (pinfunction "IN2_H2") (pintype "input"))
      (node (ref "B02") (pin "D2") (pinfunction "P$2_D2") (pintype "bidirectional"))
    )
    (net (code "225") (name "~{I_MB07}") (class "Default")
      (node (ref "A02") (pin "H2") (pinfunction "P$2_H2") (pintype "bidirectional"))
      (node (ref "A06") (pin "H2") (pinfunction "CATHODE_H2") (pintype "passive"))
      (node (ref "A10") (pin "U2") (pinfunction "IN2_U2") (pintype "input"))
      (node (ref "B02") (pin "H2") (pinfunction "P$2_H2") (pintype "bidirectional"))
    )
    (net (code "226") (name "~{I_MB08}") (class "Default")
      (node (ref "A02") (pin "M2") (pinfunction "P$2_M2") (pintype "bidirectional"))
      (node (ref "A06") (pin "M2") (pinfunction "CATHODE_M2") (pintype "passive"))
      (node (ref "A11") (pin "N2") (pinfunction "IN2_N2") (pintype "input"))
      (node (ref "B02") (pin "M2") (pinfunction "P$2_M2") (pintype "bidirectional"))
    )
    (net (code "227") (name "~{O_MB03}") (class "Default")
      (node (ref "A08") (pin "D2") (pinfunction "OUT_D2") (pintype "output"))
      (node (ref "A15") (pin "K2") (pinfunction "P$2_K2") (pintype "bidirectional"))
    )
    (net (code "228") (name "~{O_MB04}") (class "Default")
      (node (ref "A08") (pin "S2") (pinfunction "OUT_S2") (pintype "output"))
      (node (ref "A15") (pin "P2") (pinfunction "P$2_P2") (pintype "bidirectional"))
    )
    (net (code "229") (name "~{O_MB05}") (class "Default")
      (node (ref "A09") (pin "K2") (pinfunction "OUT_K2") (pintype "output"))
      (node (ref "A15") (pin "T2") (pinfunction "P$2_T2") (pintype "bidirectional"))
    )
    (net (code "230") (name "~{O_MB06}") (class "Default")
      (node (ref "A10") (pin "D2") (pinfunction "OUT_D2") (pintype "output"))
      (node (ref "A16") (pin "D2") (pinfunction "P$2_D2") (pintype "bidirectional"))
    )
    (net (code "231") (name "~{O_MB07}") (class "Default")
      (node (ref "A10") (pin "S2") (pinfunction "OUT_S2") (pintype "output"))
      (node (ref "A16") (pin "H2") (pinfunction "P$2_H2") (pintype "bidirectional"))
    )
    (net (code "232") (name "~{O_MB08}") (class "Default")
      (node (ref "A11") (pin "K2") (pinfunction "OUT_K2") (pintype "output"))
      (node (ref "A16") (pin "M2") (pinfunction "P$2_M2") (pintype "bidirectional"))
    )
  )
)
